# RX08-8-9.net
KiCad netlist of a schematic drawn in EAGLE
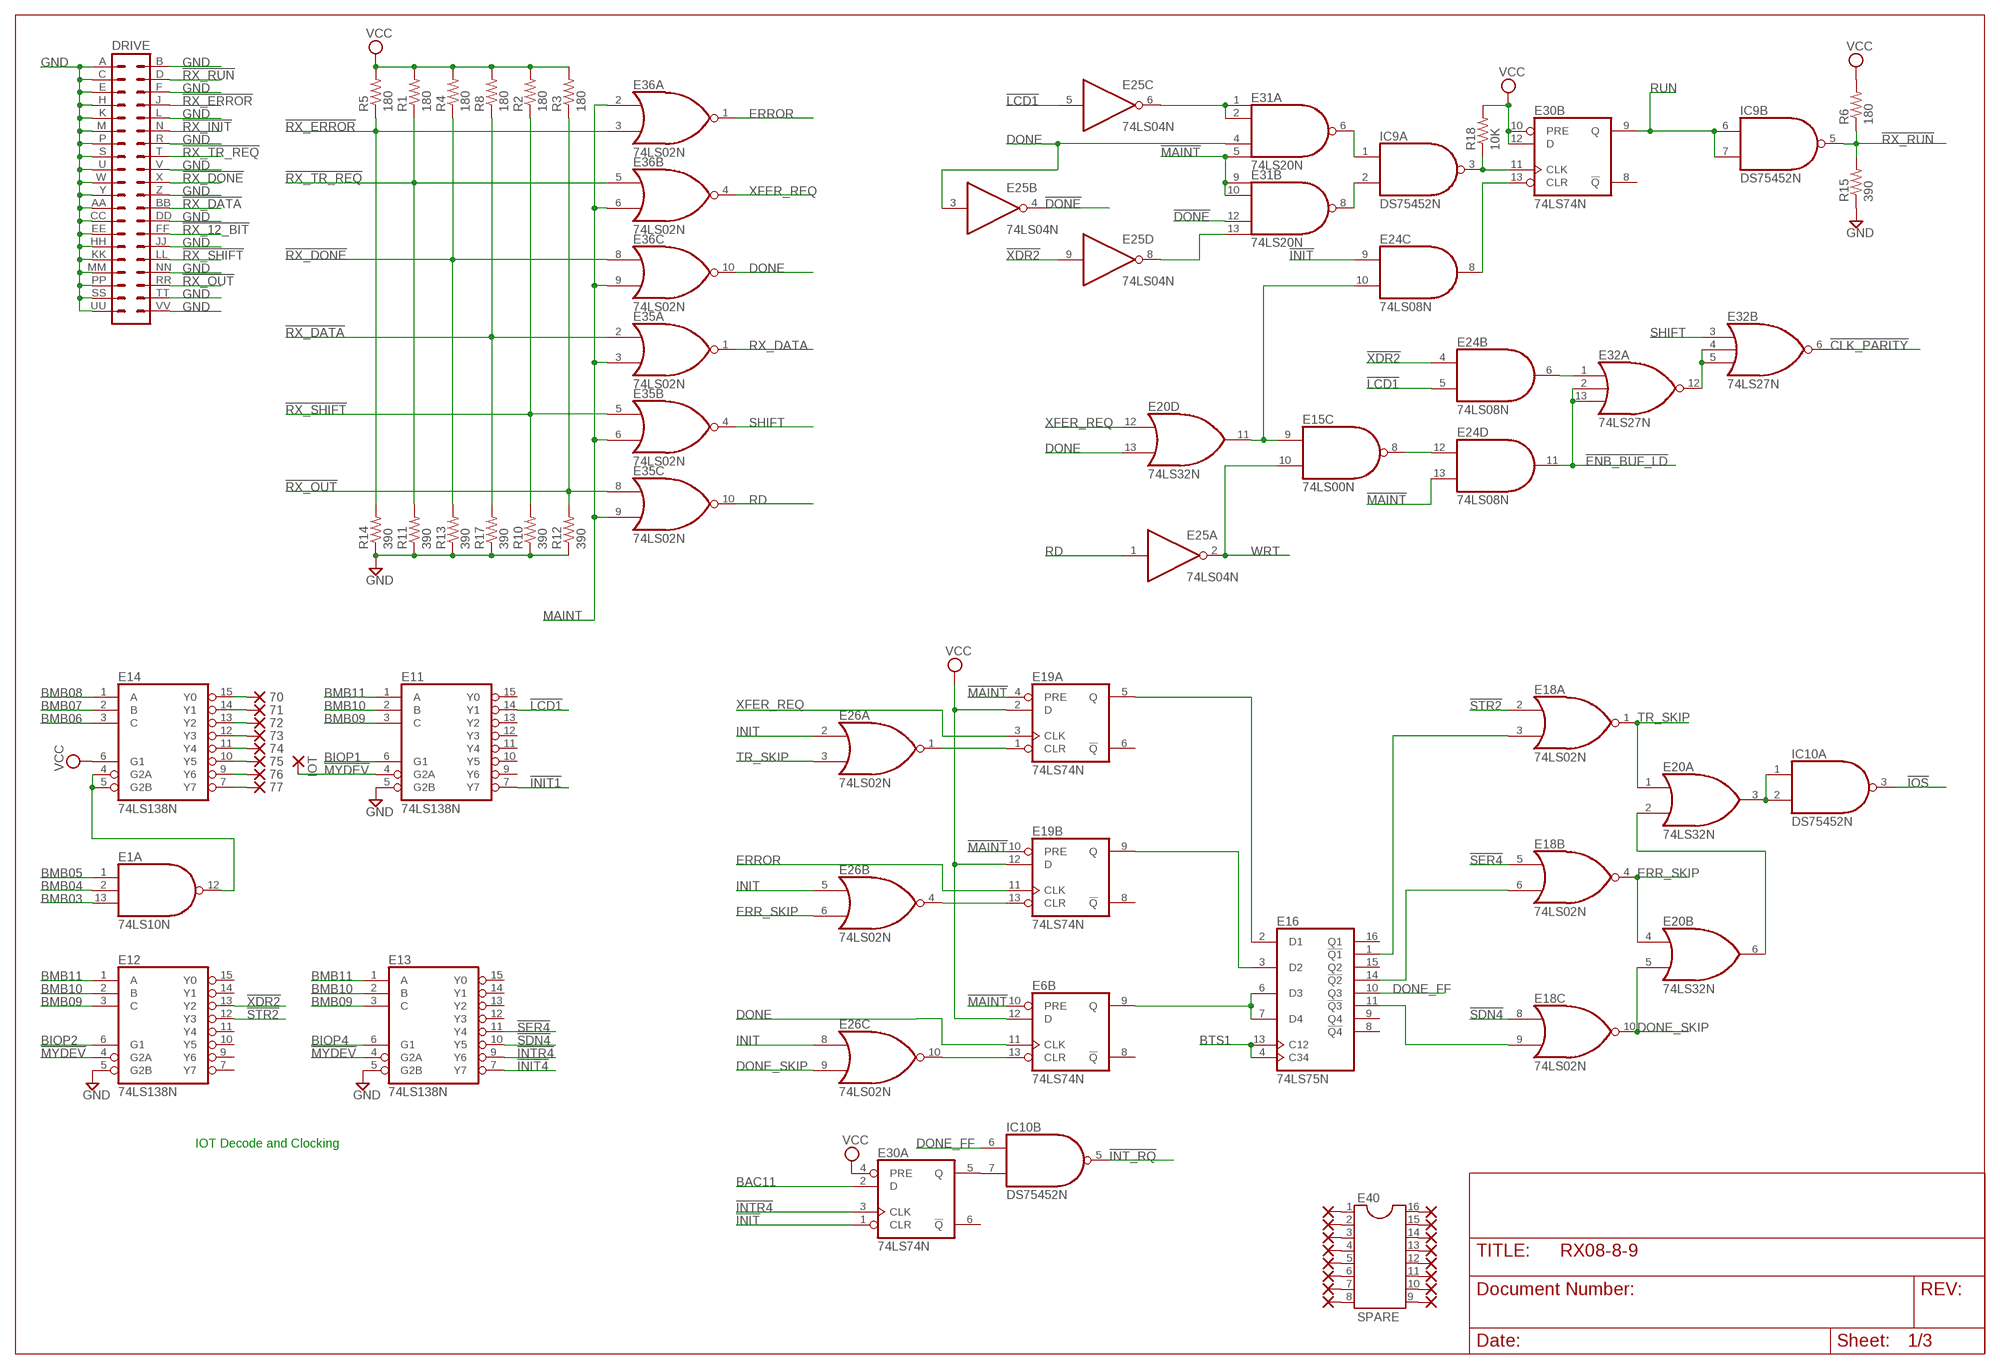
[diagram p0: schematic, sheet 1]
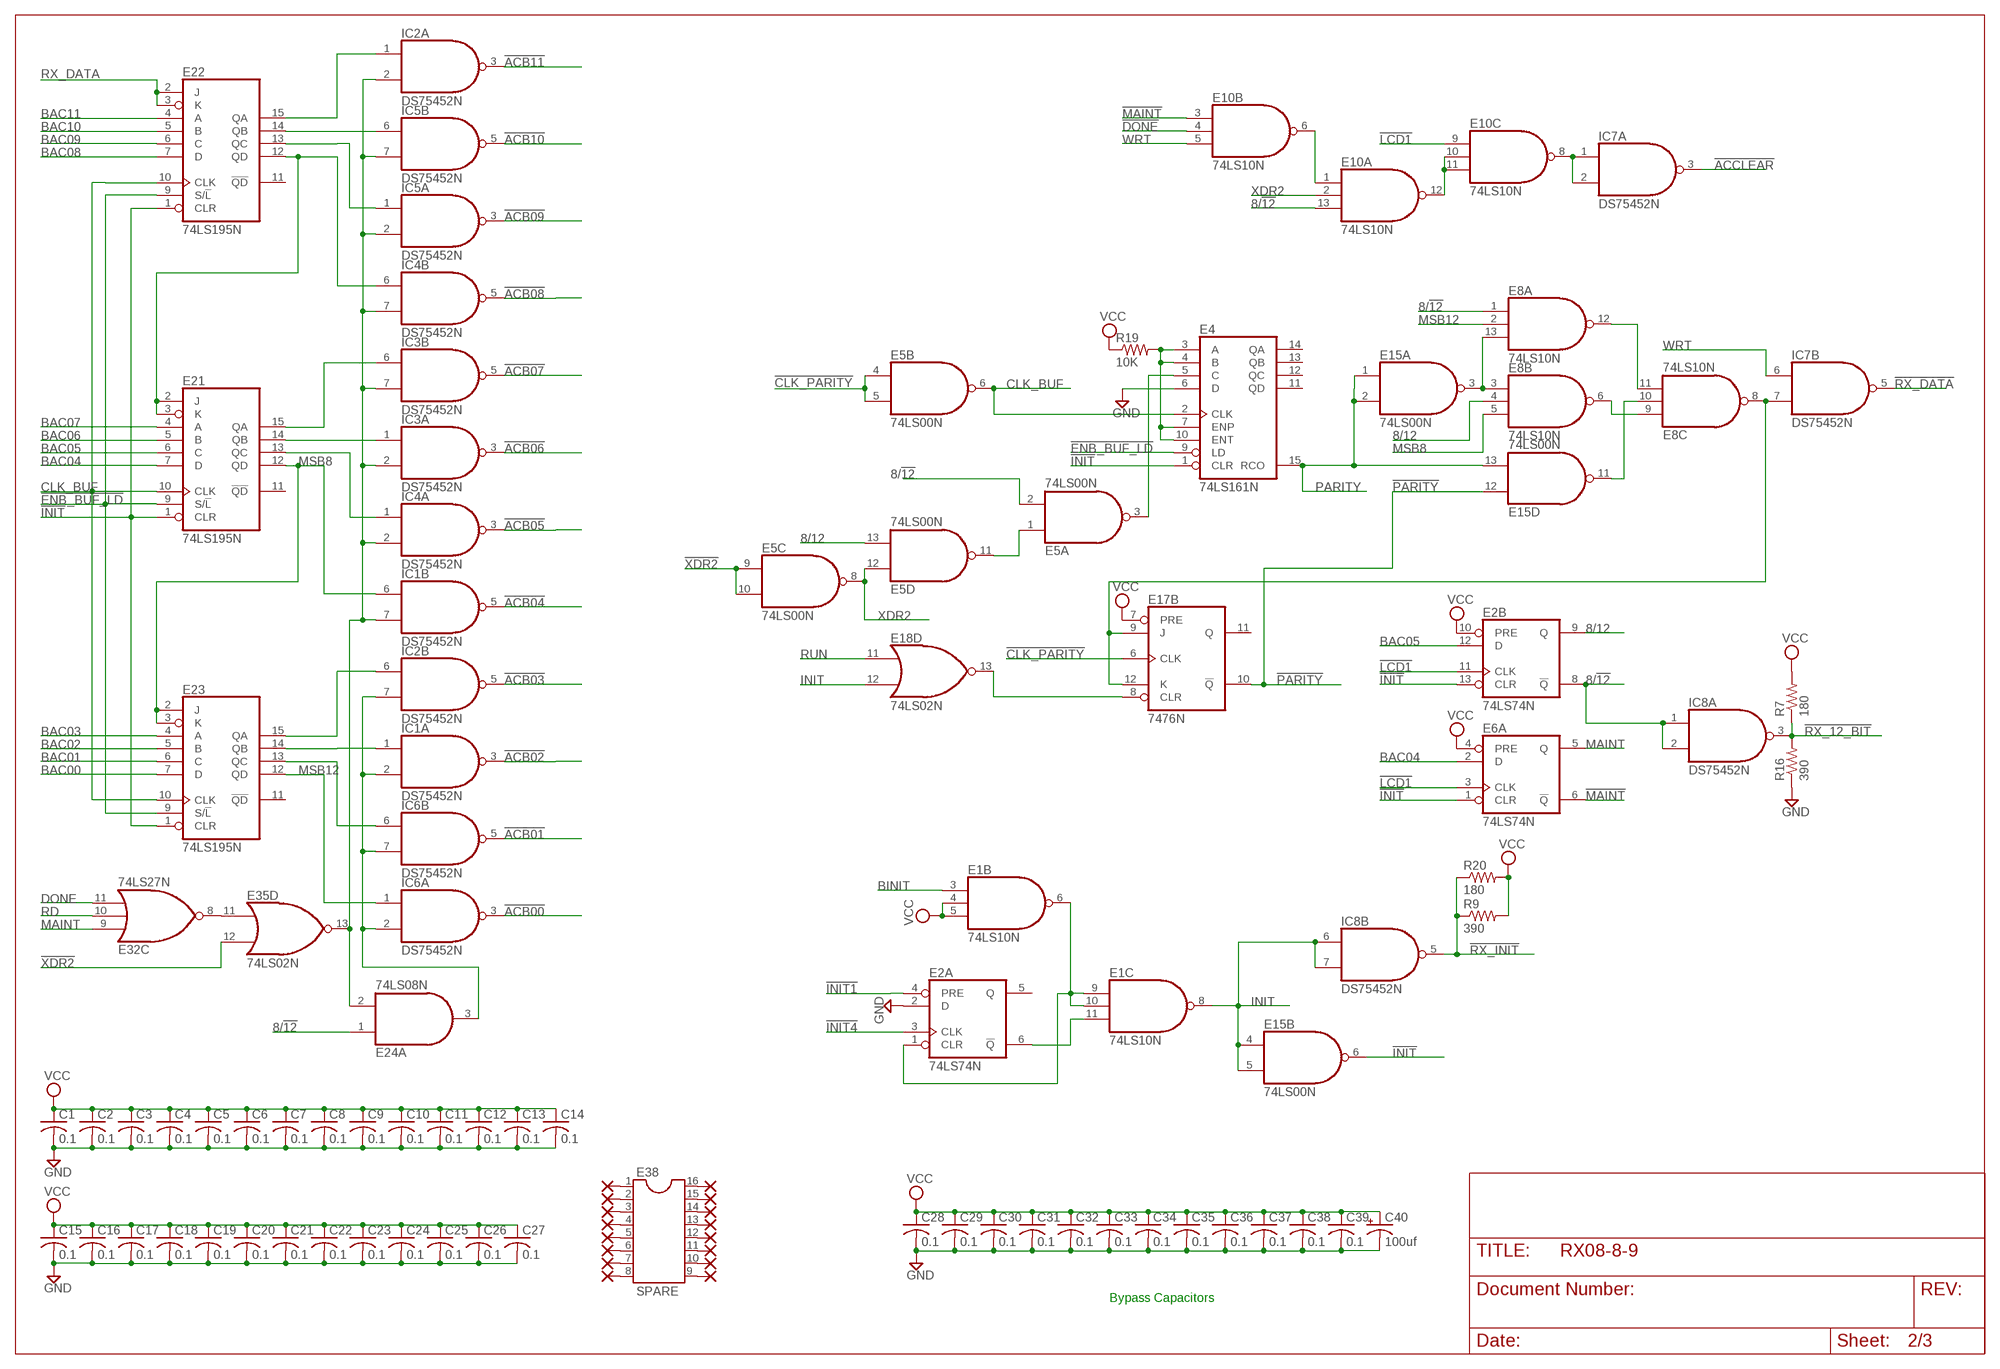
[diagram p1: schematic, sheet 2]
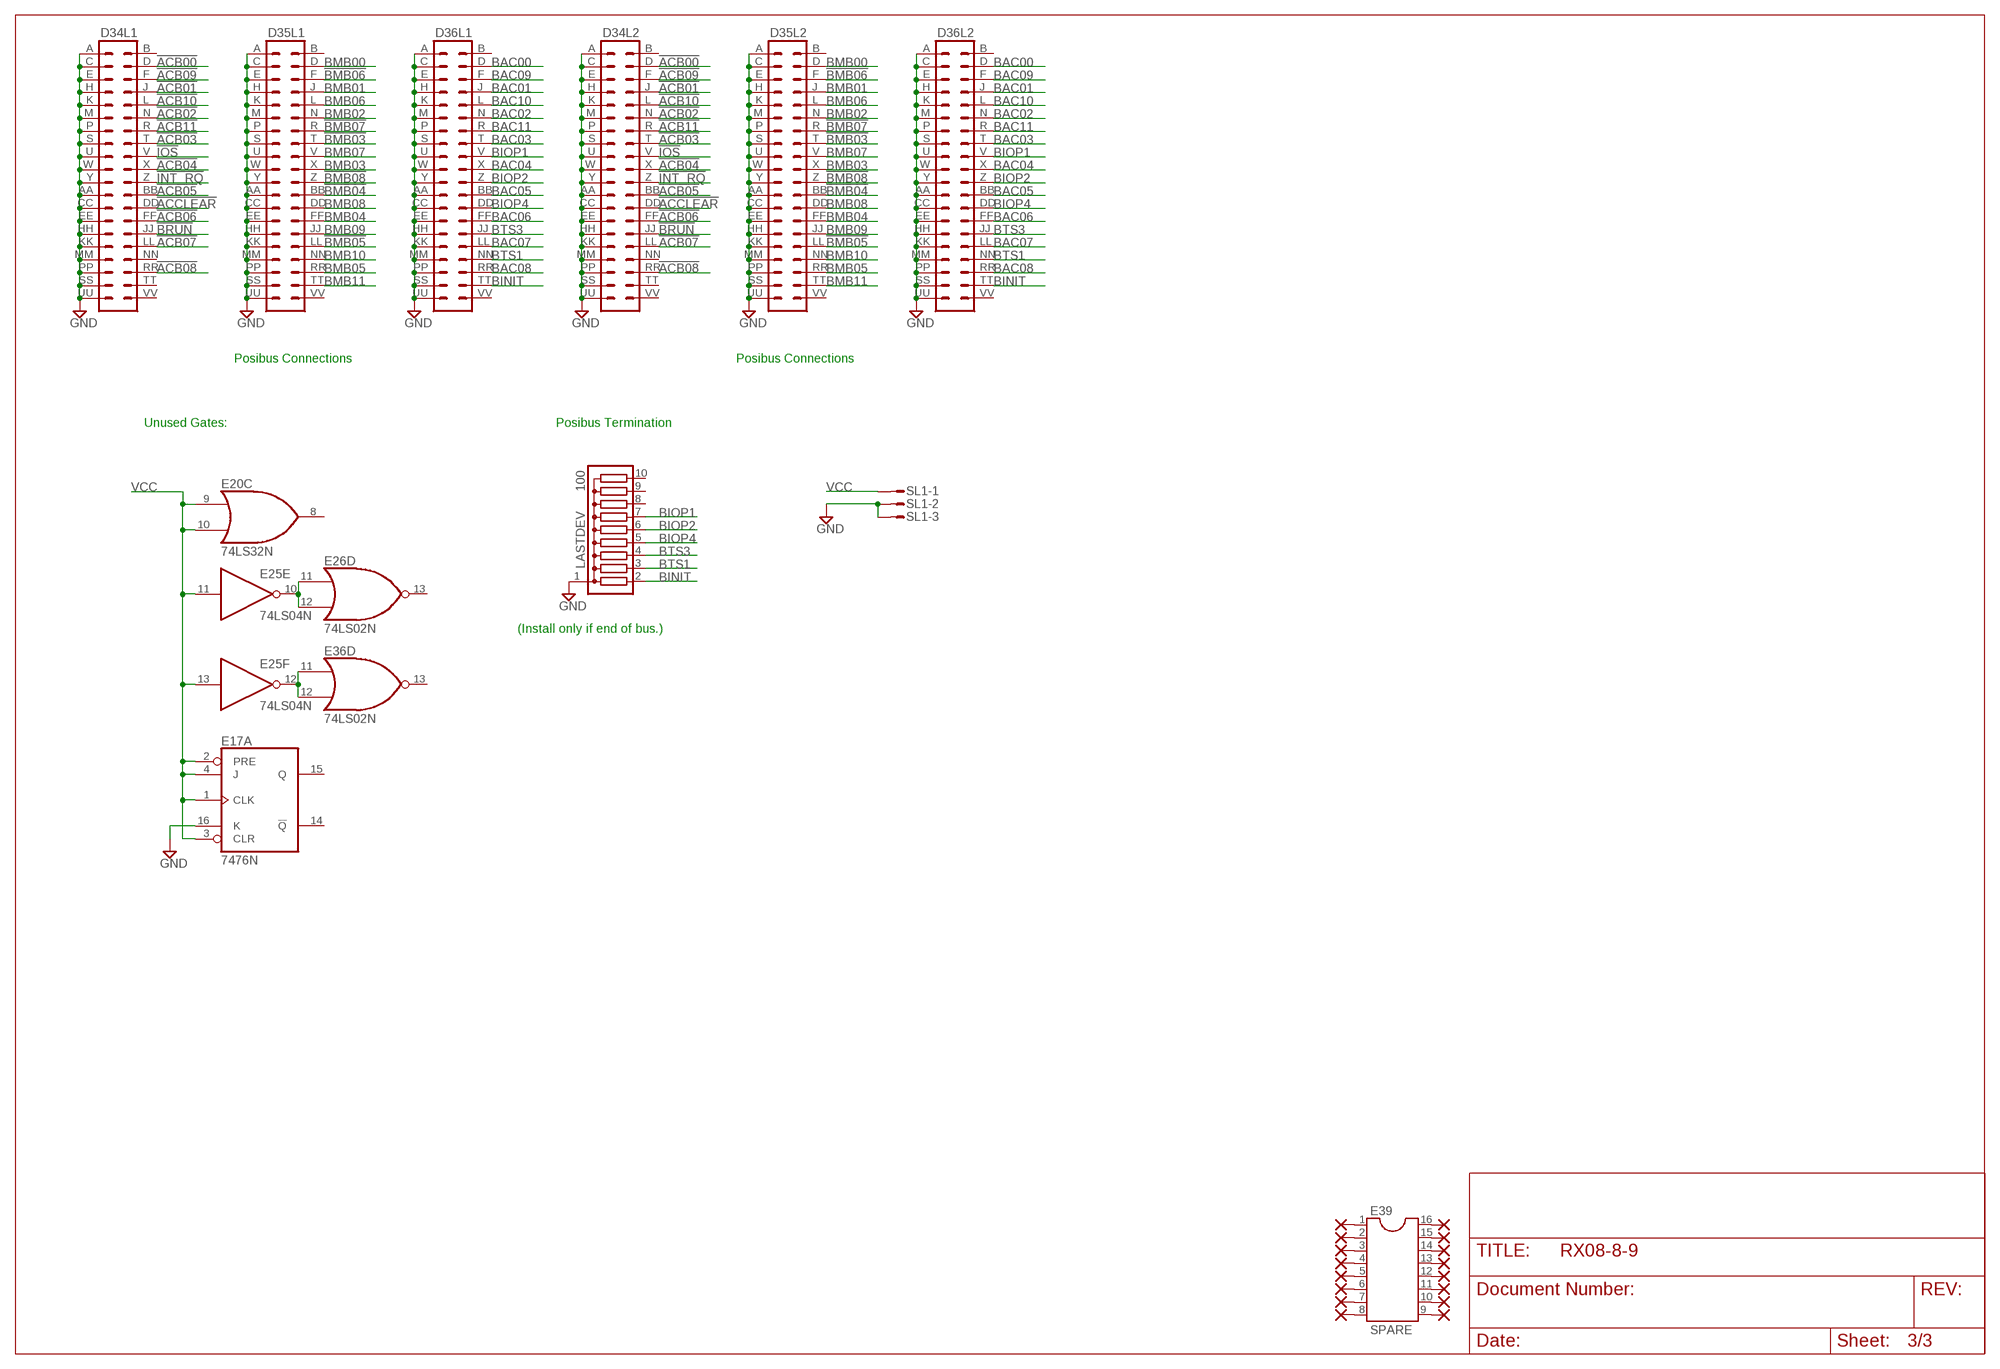
[diagram p2: schematic, sheet 3]

(export (version "E")
  (design (tool "Eeschema 10.0.6"))
  (components
    (comp (ref "D34L1")
      (value "DEC40PINV")
      (footprint "eagle-import:DEC40PINV")
      (libsource (lib "eagle-import") (part "DEC40PINV"))
    )
    (comp (ref "D34L2")
      (value "DEC40PINV")
      (footprint "eagle-import:DEC40PINV")
      (libsource (lib "eagle-import") (part "DEC40PINV"))
    )
    (comp (ref "D35L1")
      (value "DEC40PINV")
      (footprint "eagle-import:DEC40PINV")
      (libsource (lib "eagle-import") (part "DEC40PINV"))
    )
    (comp (ref "D35L2")
      (value "DEC40PINV")
      (footprint "eagle-import:DEC40PINV")
      (libsource (lib "eagle-import") (part "DEC40PINV"))
    )
    (comp (ref "D36L1")
      (value "DEC40PINV")
      (footprint "eagle-import:DEC40PINV")
      (libsource (lib "eagle-import") (part "DEC40PINV"))
    )
    (comp (ref "D36L2")
      (value "DEC40PINV")
      (footprint "eagle-import:DEC40PINV")
      (libsource (lib "eagle-import") (part "DEC40PINV"))
    )
    (comp (ref "E17")
      (value "7476N")
      (footprint "eagle-import:DIL16")
      (libsource (lib "eagle-import") (part "7476N"))
    )
    (comp (ref "E20")
      (value "74LS32N")
      (footprint "eagle-import:DIL14")
      (libsource (lib "eagle-import") (part "7432NLS"))
    )
    (comp (ref "E25")
      (value "74LS04N")
      (footprint "eagle-import:DIL14")
      (libsource (lib "eagle-import") (part "7404NLS"))
    )
    (comp (ref "E26")
      (value "74LS02N")
      (footprint "eagle-import:DIL14")
      (libsource (lib "eagle-import") (part "7402NLS"))
    )
    (comp (ref "E36")
      (value "74LS02N")
      (footprint "eagle-import:DIL14")
      (libsource (lib "eagle-import") (part "7402NLS"))
    )
    (comp (ref "E39")
      (value "SPARE")
      (footprint "eagle-import:DIL16")
      (libsource (lib "eagle-import") (part "DIL16"))
    )
    (comp (ref "LASTDEV")
      (value "100")
      (footprint "eagle-import:SIL10")
      (libsource (lib "eagle-import") (part "G09R"))
    )
    (comp (ref "PAD42")
      (value "1,6/0,8")
      (footprint "eagle-import:1,6_0,8")
      (libsource (lib "eagle-import") (part "1,6/0,8"))
    )
    (comp (ref "PAD43")
      (value "1,6/0,8")
      (footprint "eagle-import:1,6_0,8")
      (libsource (lib "eagle-import") (part "1,6/0,8"))
    )
    (comp (ref "PAD44")
      (value "1,6/0,8")
      (footprint "eagle-import:1,6_0,8")
      (libsource (lib "eagle-import") (part "1,6/0,8"))
    )
    (comp (ref "PAD45")
      (value "1,6/0,8")
      (footprint "eagle-import:1,6_0,8")
      (libsource (lib "eagle-import") (part "1,6/0,8"))
    )
    (comp (ref "PAD46")
      (value "1,6/0,8")
      (footprint "eagle-import:1,6_0,8")
      (libsource (lib "eagle-import") (part "1,6/0,8"))
    )
    (comp (ref "PAD47")
      (value "1,6/0,8")
      (footprint "eagle-import:1,6_0,8")
      (libsource (lib "eagle-import") (part "1,6/0,8"))
    )
    (comp (ref "PAD48")
      (value "1,6/0,8")
      (footprint "eagle-import:1,6_0,8")
      (libsource (lib "eagle-import") (part "1,6/0,8"))
    )
    (comp (ref "PAD49")
      (value "1,6/0,8")
      (footprint "eagle-import:1,6_0,8")
      (libsource (lib "eagle-import") (part "1,6/0,8"))
    )
    (comp (ref "PAD50")
      (value "1,6/0,8")
      (footprint "eagle-import:1,6_0,8")
      (libsource (lib "eagle-import") (part "1,6/0,8"))
    )
    (comp (ref "PAD51")
      (value "1,6/0,8")
      (footprint "eagle-import:1,6_0,8")
      (libsource (lib "eagle-import") (part "1,6/0,8"))
    )
    (comp (ref "PAD52")
      (value "1,6/0,8")
      (footprint "eagle-import:1,6_0,8")
      (libsource (lib "eagle-import") (part "1,6/0,8"))
    )
    (comp (ref "PAD53")
      (value "1,6/0,8")
      (footprint "eagle-import:1,6_0,8")
      (libsource (lib "eagle-import") (part "1,6/0,8"))
    )
    (comp (ref "PAD54")
      (value "1,6/0,8")
      (footprint "eagle-import:1,6_0,8")
      (libsource (lib "eagle-import") (part "1,6/0,8"))
    )
    (comp (ref "PAD55")
      (value "1,6/0,8")
      (footprint "eagle-import:1,6_0,8")
      (libsource (lib "eagle-import") (part "1,6/0,8"))
    )
    (comp (ref "PAD56")
      (value "1,6/0,8")
      (footprint "eagle-import:1,6_0,8")
      (libsource (lib "eagle-import") (part "1,6/0,8"))
    )
    (comp (ref "PAD57")
      (value "1,6/0,8")
      (footprint "eagle-import:1,6_0,8")
      (libsource (lib "eagle-import") (part "1,6/0,8"))
    )
    (comp (ref "SL1")
      (value "MA04S")
      (footprint "eagle-import:04PA")
      (libsource (lib "eagle-import") (part "MA04S"))
    )
    (comp (ref "C1")
      (value "0.1")
      (footprint "eagle-import:C050-025X075")
      (libsource (lib "eagle-import") (part "C-US050-025X075"))
    )
    (comp (ref "C2")
      (value "0.1")
      (footprint "eagle-import:C050-025X075")
      (libsource (lib "eagle-import") (part "C-US050-025X075"))
    )
    (comp (ref "C3")
      (value "0.1")
      (footprint "eagle-import:C050-025X075")
      (libsource (lib "eagle-import") (part "C-US050-025X075"))
    )
    (comp (ref "C4")
      (value "0.1")
      (footprint "eagle-import:C050-025X075")
      (libsource (lib "eagle-import") (part "C-US050-025X075"))
    )
    (comp (ref "C5")
      (value "0.1")
      (footprint "eagle-import:C050-025X075")
      (libsource (lib "eagle-import") (part "C-US050-025X075"))
    )
    (comp (ref "C6")
      (value "0.1")
      (footprint "eagle-import:C050-025X075")
      (libsource (lib "eagle-import") (part "C-US050-025X075"))
    )
    (comp (ref "C7")
      (value "0.1")
      (footprint "eagle-import:C050-025X075")
      (libsource (lib "eagle-import") (part "C-US050-025X075"))
    )
    (comp (ref "C8")
      (value "0.1")
      (footprint "eagle-import:C050-025X075")
      (libsource (lib "eagle-import") (part "C-US050-025X075"))
    )
    (comp (ref "C9")
      (value "0.1")
      (footprint "eagle-import:C050-025X075")
      (libsource (lib "eagle-import") (part "C-US050-025X075"))
    )
    (comp (ref "C10")
      (value "0.1")
      (footprint "eagle-import:C050-025X075")
      (libsource (lib "eagle-import") (part "C-US050-025X075"))
    )
    (comp (ref "C11")
      (value "0.1")
      (footprint "eagle-import:C050-025X075")
      (libsource (lib "eagle-import") (part "C-US050-025X075"))
    )
    (comp (ref "C12")
      (value "0.1")
      (footprint "eagle-import:C050-025X075")
      (libsource (lib "eagle-import") (part "C-US050-025X075"))
    )
    (comp (ref "C13")
      (value "0.1")
      (footprint "eagle-import:C050-025X075")
      (libsource (lib "eagle-import") (part "C-US050-025X075"))
    )
    (comp (ref "C14")
      (value "0.1")
      (footprint "eagle-import:C050-025X075")
      (libsource (lib "eagle-import") (part "C-US050-025X075"))
    )
    (comp (ref "C15")
      (value "0.1")
      (footprint "eagle-import:C050-025X075")
      (libsource (lib "eagle-import") (part "C-US050-025X075"))
    )
    (comp (ref "C16")
      (value "0.1")
      (footprint "eagle-import:C050-025X075")
      (libsource (lib "eagle-import") (part "C-US050-025X075"))
    )
    (comp (ref "C17")
      (value "0.1")
      (footprint "eagle-import:C050-025X075")
      (libsource (lib "eagle-import") (part "C-US050-025X075"))
    )
    (comp (ref "C18")
      (value "0.1")
      (footprint "eagle-import:C050-025X075")
      (libsource (lib "eagle-import") (part "C-US050-025X075"))
    )
    (comp (ref "C19")
      (value "0.1")
      (footprint "eagle-import:C050-025X075")
      (libsource (lib "eagle-import") (part "C-US050-025X075"))
    )
    (comp (ref "C20")
      (value "0.1")
      (footprint "eagle-import:C050-025X075")
      (libsource (lib "eagle-import") (part "C-US050-025X075"))
    )
    (comp (ref "C21")
      (value "0.1")
      (footprint "eagle-import:C050-025X075")
      (libsource (lib "eagle-import") (part "C-US050-025X075"))
    )
    (comp (ref "C22")
      (value "0.1")
      (footprint "eagle-import:C050-025X075")
      (libsource (lib "eagle-import") (part "C-US050-025X075"))
    )
    (comp (ref "C23")
      (value "0.1")
      (footprint "eagle-import:C050-025X075")
      (libsource (lib "eagle-import") (part "C-US050-025X075"))
    )
    (comp (ref "C24")
      (value "0.1")
      (footprint "eagle-import:C050-025X075")
      (libsource (lib "eagle-import") (part "C-US050-025X075"))
    )
    (comp (ref "C25")
      (value "0.1")
      (footprint "eagle-import:C050-025X075")
      (libsource (lib "eagle-import") (part "C-US050-025X075"))
    )
    (comp (ref "C26")
      (value "0.1")
      (footprint "eagle-import:C050-025X075")
      (libsource (lib "eagle-import") (part "C-US050-025X075"))
    )
    (comp (ref "C27")
      (value "0.1")
      (footprint "eagle-import:C050-025X075")
      (libsource (lib "eagle-import") (part "C-US050-025X075"))
    )
    (comp (ref "C28")
      (value "0.1")
      (footprint "eagle-import:C050-025X075")
      (libsource (lib "eagle-import") (part "C-US050-025X075"))
    )
    (comp (ref "C29")
      (value "0.1")
      (footprint "eagle-import:C050-025X075")
      (libsource (lib "eagle-import") (part "C-US050-025X075"))
    )
    (comp (ref "C30")
      (value "0.1")
      (footprint "eagle-import:C050-025X075")
      (libsource (lib "eagle-import") (part "C-US050-025X075"))
    )
    (comp (ref "C31")
      (value "0.1")
      (footprint "eagle-import:C050-025X075")
      (libsource (lib "eagle-import") (part "C-US050-025X075"))
    )
    (comp (ref "C32")
      (value "0.1")
      (footprint "eagle-import:C050-025X075")
      (libsource (lib "eagle-import") (part "C-US050-025X075"))
    )
    (comp (ref "C33")
      (value "0.1")
      (footprint "eagle-import:C050-025X075")
      (libsource (lib "eagle-import") (part "C-US050-025X075"))
    )
    (comp (ref "C34")
      (value "0.1")
      (footprint "eagle-import:C050-025X075")
      (libsource (lib "eagle-import") (part "C-US050-025X075"))
    )
    (comp (ref "C35")
      (value "0.1")
      (footprint "eagle-import:C050-025X075")
      (libsource (lib "eagle-import") (part "C-US050-025X075"))
    )
    (comp (ref "C36")
      (value "0.1")
      (footprint "eagle-import:C050-025X075")
      (libsource (lib "eagle-import") (part "C-US050-025X075"))
    )
    (comp (ref "C37")
      (value "0.1")
      (footprint "eagle-import:C050-025X075")
      (libsource (lib "eagle-import") (part "C-US050-025X075"))
    )
    (comp (ref "C38")
      (value "0.1")
      (footprint "eagle-import:C050-025X075")
      (libsource (lib "eagle-import") (part "C-US050-025X075"))
    )
    (comp (ref "C39")
      (value "0.1")
      (footprint "eagle-import:C050-025X075")
      (libsource (lib "eagle-import") (part "C-US050-025X075"))
    )
    (comp (ref "C40")
      (value "100uf")
      (footprint "eagle-import:E22-9")
      (libsource (lib "eagle-import") (part "CPOL-USE22-9AXIAL"))
    )
    (comp (ref "E1")
      (value "74LS10N")
      (footprint "eagle-import:DIL14")
      (libsource (lib "eagle-import") (part "7410NLS"))
    )
    (comp (ref "E2")
      (value "74LS74N")
      (footprint "eagle-import:DIL14")
      (libsource (lib "eagle-import") (part "7474NLS"))
    )
    (comp (ref "E4")
      (value "74LS161N")
      (footprint "eagle-import:DIL16")
      (libsource (lib "eagle-import") (part "74161NLS"))
    )
    (comp (ref "E5")
      (value "74LS00N")
      (footprint "eagle-import:DIL14")
      (libsource (lib "eagle-import") (part "7400NLS"))
    )
    (comp (ref "E6")
      (value "74LS74N")
      (footprint "eagle-import:DIL14")
      (libsource (lib "eagle-import") (part "7474NLS"))
    )
    (comp (ref "E8")
      (value "74LS10N")
      (footprint "eagle-import:DIL14")
      (libsource (lib "eagle-import") (part "7410NLS"))
    )
    (comp (ref "E10")
      (value "74LS10N")
      (footprint "eagle-import:DIL14")
      (libsource (lib "eagle-import") (part "7410NLS"))
    )
    (comp (ref "E15")
      (value "74LS00N")
      (footprint "eagle-import:DIL14")
      (libsource (lib "eagle-import") (part "7400NLS"))
    )
    (comp (ref "E18")
      (value "74LS02N")
      (footprint "eagle-import:DIL14")
      (libsource (lib "eagle-import") (part "7402NLS"))
    )
    (comp (ref "E21")
      (value "74LS195N")
      (footprint "eagle-import:DIL16")
      (libsource (lib "eagle-import") (part "74195NLS"))
    )
    (comp (ref "E22")
      (value "74LS195N")
      (footprint "eagle-import:DIL16")
      (libsource (lib "eagle-import") (part "74195NLS"))
    )
    (comp (ref "E23")
      (value "74LS195N")
      (footprint "eagle-import:DIL16")
      (libsource (lib "eagle-import") (part "74195NLS"))
    )
    (comp (ref "E24")
      (value "74LS08N")
      (footprint "eagle-import:DIL14")
      (libsource (lib "eagle-import") (part "7408NLS"))
    )
    (comp (ref "E32")
      (value "74LS27N")
      (footprint "eagle-import:DIL14")
      (libsource (lib "eagle-import") (part "7427NLS"))
    )
    (comp (ref "E35")
      (value "74LS02N")
      (footprint "eagle-import:DIL14")
      (libsource (lib "eagle-import") (part "7402NLS"))
    )
    (comp (ref "E38")
      (value "SPARE")
      (footprint "eagle-import:DIL16")
      (libsource (lib "eagle-import") (part "DIL16"))
    )
    (comp (ref "IC1")
      (value "DS75452N")
      (footprint "eagle-import:DIL08")
      (libsource (lib "eagle-import") (part "DS75452N"))
    )
    (comp (ref "IC2")
      (value "DS75452N")
      (footprint "eagle-import:DIL08")
      (libsource (lib "eagle-import") (part "DS75452N"))
    )
    (comp (ref "IC3")
      (value "DS75452N")
      (footprint "eagle-import:DIL08")
      (libsource (lib "eagle-import") (part "DS75452N"))
    )
    (comp (ref "IC4")
      (value "DS75452N")
      (footprint "eagle-import:DIL08")
      (libsource (lib "eagle-import") (part "DS75452N"))
    )
    (comp (ref "IC5")
      (value "DS75452N")
      (footprint "eagle-import:DIL08")
      (libsource (lib "eagle-import") (part "DS75452N"))
    )
    (comp (ref "IC6")
      (value "DS75452N")
      (footprint "eagle-import:DIL08")
      (libsource (lib "eagle-import") (part "DS75452N"))
    )
    (comp (ref "IC7")
      (value "DS75452N")
      (footprint "eagle-import:DIL08")
      (libsource (lib "eagle-import") (part "DS75452N"))
    )
    (comp (ref "IC8")
      (value "DS75452N")
      (footprint "eagle-import:DIL08")
      (libsource (lib "eagle-import") (part "DS75452N"))
    )
    (comp (ref "PAD10")
      (value "1,6/0,8")
      (footprint "eagle-import:1,6_0,8")
      (libsource (lib "eagle-import") (part "1,6/0,8"))
    )
    (comp (ref "PAD11")
      (value "1,6/0,8")
      (footprint "eagle-import:1,6_0,8")
      (libsource (lib "eagle-import") (part "1,6/0,8"))
    )
    (comp (ref "PAD12")
      (value "1,6/0,8")
      (footprint "eagle-import:1,6_0,8")
      (libsource (lib "eagle-import") (part "1,6/0,8"))
    )
    (comp (ref "PAD13")
      (value "1,6/0,8")
      (footprint "eagle-import:1,6_0,8")
      (libsource (lib "eagle-import") (part "1,6/0,8"))
    )
    (comp (ref "PAD14")
      (value "1,6/0,8")
      (footprint "eagle-import:1,6_0,8")
      (libsource (lib "eagle-import") (part "1,6/0,8"))
    )
    (comp (ref "PAD15")
      (value "1,6/0,8")
      (footprint "eagle-import:1,6_0,8")
      (libsource (lib "eagle-import") (part "1,6/0,8"))
    )
    (comp (ref "PAD16")
      (value "1,6/0,8")
      (footprint "eagle-import:1,6_0,8")
      (libsource (lib "eagle-import") (part "1,6/0,8"))
    )
    (comp (ref "PAD17")
      (value "1,6/0,8")
      (footprint "eagle-import:1,6_0,8")
      (libsource (lib "eagle-import") (part "1,6/0,8"))
    )
    (comp (ref "PAD20")
      (value "1,6/0,8")
      (footprint "eagle-import:1,6_0,8")
      (libsource (lib "eagle-import") (part "1,6/0,8"))
    )
    (comp (ref "PAD21")
      (value "1,6/0,8")
      (footprint "eagle-import:1,6_0,8")
      (libsource (lib "eagle-import") (part "1,6/0,8"))
    )
    (comp (ref "PAD22")
      (value "1,6/0,8")
      (footprint "eagle-import:1,6_0,8")
      (libsource (lib "eagle-import") (part "1,6/0,8"))
    )
    (comp (ref "PAD23")
      (value "1,6/0,8")
      (footprint "eagle-import:1,6_0,8")
      (libsource (lib "eagle-import") (part "1,6/0,8"))
    )
    (comp (ref "PAD24")
      (value "1,6/0,8")
      (footprint "eagle-import:1,6_0,8")
      (libsource (lib "eagle-import") (part "1,6/0,8"))
    )
    (comp (ref "PAD25")
      (value "1,6/0,8")
      (footprint "eagle-import:1,6_0,8")
      (libsource (lib "eagle-import") (part "1,6/0,8"))
    )
    (comp (ref "PAD26")
      (value "1,6/0,8")
      (footprint "eagle-import:1,6_0,8")
      (libsource (lib "eagle-import") (part "1,6/0,8"))
    )
    (comp (ref "PAD27")
      (value "1,6/0,8")
      (footprint "eagle-import:1,6_0,8")
      (libsource (lib "eagle-import") (part "1,6/0,8"))
    )
    (comp (ref "R7")
      (value "180")
      (footprint "eagle-import:0207_10")
      (libsource (lib "eagle-import") (part "R-US_0207/10"))
    )
    (comp (ref "R9")
      (value "390")
      (footprint "eagle-import:0207_10")
      (libsource (lib "eagle-import") (part "R-US_0207/10"))
    )
    (comp (ref "R16")
      (value "390")
      (footprint "eagle-import:0207_10")
      (libsource (lib "eagle-import") (part "R-US_0207/10"))
    )
    (comp (ref "R19")
      (value "10K")
      (footprint "eagle-import:0207_10")
      (libsource (lib "eagle-import") (part "R-US_0207/10"))
    )
    (comp (ref "R20")
      (value "180")
      (footprint "eagle-import:0207_10")
      (libsource (lib "eagle-import") (part "R-US_0207/10"))
    )
    (comp (ref "70")
      (value "1,6/0,8")
      (footprint "eagle-import:1,6_0,8")
      (libsource (lib "eagle-import") (part "1,6/0,8"))
    )
    (comp (ref "71")
      (value "1,6/0,8")
      (footprint "eagle-import:1,6_0,8")
      (libsource (lib "eagle-import") (part "1,6/0,8"))
    )
    (comp (ref "72")
      (value "1,6/0,8")
      (footprint "eagle-import:1,6_0,8")
      (libsource (lib "eagle-import") (part "1,6/0,8"))
    )
    (comp (ref "73")
      (value "1,6/0,8")
      (footprint "eagle-import:1,6_0,8")
      (libsource (lib "eagle-import") (part "1,6/0,8"))
    )
    (comp (ref "74")
      (value "1,6/0,8")
      (footprint "eagle-import:1,6_0,8")
      (libsource (lib "eagle-import") (part "1,6/0,8"))
    )
    (comp (ref "75")
      (value "1,6/0,8")
      (footprint "eagle-import:1,6_0,8")
      (libsource (lib "eagle-import") (part "1,6/0,8"))
    )
    (comp (ref "76")
      (value "1,6/0,8")
      (footprint "eagle-import:1,6_0,8")
      (libsource (lib "eagle-import") (part "1,6/0,8"))
    )
    (comp (ref "77")
      (value "1,6/0,8")
      (footprint "eagle-import:1,6_0,8")
      (libsource (lib "eagle-import") (part "1,6/0,8"))
    )
    (comp (ref "DRIVE")
      (value "DEC40PINV")
      (footprint "eagle-import:DEC40PINV")
      (libsource (lib "eagle-import") (part "DEC40PINV"))
    )
    (comp (ref "E11")
      (value "74LS138N")
      (footprint "eagle-import:DIL16")
      (libsource (lib "eagle-import") (part "74138NLS"))
    )
    (comp (ref "E12")
      (value "74LS138N")
      (footprint "eagle-import:DIL16")
      (libsource (lib "eagle-import") (part "74138NLS"))
    )
    (comp (ref "E13")
      (value "74LS138N")
      (footprint "eagle-import:DIL16")
      (libsource (lib "eagle-import") (part "74138NLS"))
    )
    (comp (ref "E14")
      (value "74LS138N")
      (footprint "eagle-import:DIL16")
      (libsource (lib "eagle-import") (part "74138NLS"))
    )
    (comp (ref "E16")
      (value "74LS75N")
      (footprint "eagle-import:DIL16")
      (libsource (lib "eagle-import") (part "7475NLS"))
    )
    (comp (ref "E19")
      (value "74LS74N")
      (footprint "eagle-import:DIL14")
      (libsource (lib "eagle-import") (part "7474NLS"))
    )
    (comp (ref "E30")
      (value "74LS74N")
      (footprint "eagle-import:DIL14")
      (libsource (lib "eagle-import") (part "7474NLS"))
    )
    (comp (ref "E31")
      (value "74LS20N")
      (footprint "eagle-import:DIL14")
      (libsource (lib "eagle-import") (part "7420NLS"))
    )
    (comp (ref "E40")
      (value "SPARE")
      (footprint "eagle-import:DIL16")
      (libsource (lib "eagle-import") (part "DIL16"))
    )
    (comp (ref "IC9")
      (value "DS75452N")
      (footprint "eagle-import:DIL08")
      (libsource (lib "eagle-import") (part "DS75452N"))
    )
    (comp (ref "IC10")
      (value "DS75452N")
      (footprint "eagle-import:DIL08")
      (libsource (lib "eagle-import") (part "DS75452N"))
    )
    (comp (ref "IOT")
      (value "1,6/0,8")
      (footprint "eagle-import:1,6_0,8")
      (libsource (lib "eagle-import") (part "1,6/0,8"))
    )
    (comp (ref "PAD18")
      (value "1,6/0,8")
      (footprint "eagle-import:1,6_0,8")
      (libsource (lib "eagle-import") (part "1,6/0,8"))
    )
    (comp (ref "PAD19")
      (value "1,6/0,8")
      (footprint "eagle-import:1,6_0,8")
      (libsource (lib "eagle-import") (part "1,6/0,8"))
    )
    (comp (ref "PAD28")
      (value "1,6/0,8")
      (footprint "eagle-import:1,6_0,8")
      (libsource (lib "eagle-import") (part "1,6/0,8"))
    )
    (comp (ref "PAD29")
      (value "1,6/0,8")
      (footprint "eagle-import:1,6_0,8")
      (libsource (lib "eagle-import") (part "1,6/0,8"))
    )
    (comp (ref "PAD30")
      (value "1,6/0,8")
      (footprint "eagle-import:1,6_0,8")
      (libsource (lib "eagle-import") (part "1,6/0,8"))
    )
    (comp (ref "PAD31")
      (value "1,6/0,8")
      (footprint "eagle-import:1,6_0,8")
      (libsource (lib "eagle-import") (part "1,6/0,8"))
    )
    (comp (ref "PAD32")
      (value "1,6/0,8")
      (footprint "eagle-import:1,6_0,8")
      (libsource (lib "eagle-import") (part "1,6/0,8"))
    )
    (comp (ref "PAD33")
      (value "1,6/0,8")
      (footprint "eagle-import:1,6_0,8")
      (libsource (lib "eagle-import") (part "1,6/0,8"))
    )
    (comp (ref "PAD34")
      (value "1,6/0,8")
      (footprint "eagle-import:1,6_0,8")
      (libsource (lib "eagle-import") (part "1,6/0,8"))
    )
    (comp (ref "PAD35")
      (value "1,6/0,8")
      (footprint "eagle-import:1,6_0,8")
      (libsource (lib "eagle-import") (part "1,6/0,8"))
    )
    (comp (ref "PAD36")
      (value "1,6/0,8")
      (footprint "eagle-import:1,6_0,8")
      (libsource (lib "eagle-import") (part "1,6/0,8"))
    )
    (comp (ref "PAD37")
      (value "1,6/0,8")
      (footprint "eagle-import:1,6_0,8")
      (libsource (lib "eagle-import") (part "1,6/0,8"))
    )
    (comp (ref "PAD38")
      (value "1,6/0,8")
      (footprint "eagle-import:1,6_0,8")
      (libsource (lib "eagle-import") (part "1,6/0,8"))
    )
    (comp (ref "PAD39")
      (value "1,6/0,8")
      (footprint "eagle-import:1,6_0,8")
      (libsource (lib "eagle-import") (part "1,6/0,8"))
    )
    (comp (ref "PAD40")
      (value "1,6/0,8")
      (footprint "eagle-import:1,6_0,8")
      (libsource (lib "eagle-import") (part "1,6/0,8"))
    )
    (comp (ref "PAD41")
      (value "1,6/0,8")
      (footprint "eagle-import:1,6_0,8")
      (libsource (lib "eagle-import") (part "1,6/0,8"))
    )
    (comp (ref "R1")
      (value "180")
      (footprint "eagle-import:0207_10")
      (libsource (lib "eagle-import") (part "R-US_0207/10"))
    )
    (comp (ref "R2")
      (value "180")
      (footprint "eagle-import:0207_10")
      (libsource (lib "eagle-import") (part "R-US_0207/10"))
    )
    (comp (ref "R3")
      (value "180")
      (footprint "eagle-import:0207_10")
      (libsource (lib "eagle-import") (part "R-US_0207/10"))
    )
    (comp (ref "R4")
      (value "180")
      (footprint "eagle-import:0207_10")
      (libsource (lib "eagle-import") (part "R-US_0207/10"))
    )
    (comp (ref "R5")
      (value "180")
      (footprint "eagle-import:0207_10")
      (libsource (lib "eagle-import") (part "R-US_0207/10"))
    )
    (comp (ref "R6")
      (value "180")
      (footprint "eagle-import:0207_10")
      (libsource (lib "eagle-import") (part "R-US_0207/10"))
    )
    (comp (ref "R8")
      (value "180")
      (footprint "eagle-import:0207_10")
      (libsource (lib "eagle-import") (part "R-US_0207/10"))
    )
    (comp (ref "R10")
      (value "390")
      (footprint "eagle-import:0207_10")
      (libsource (lib "eagle-import") (part "R-US_0207/10"))
    )
    (comp (ref "R11")
      (value "390")
      (footprint "eagle-import:0207_10")
      (libsource (lib "eagle-import") (part "R-US_0207/10"))
    )
    (comp (ref "R12")
      (value "390")
      (footprint "eagle-import:0207_10")
      (libsource (lib "eagle-import") (part "R-US_0207/10"))
    )
    (comp (ref "R13")
      (value "390")
      (footprint "eagle-import:0207_10")
      (libsource (lib "eagle-import") (part "R-US_0207/10"))
    )
    (comp (ref "R14")
      (value "390")
      (footprint "eagle-import:0207_10")
      (libsource (lib "eagle-import") (part "R-US_0207/10"))
    )
    (comp (ref "R15")
      (value "390")
      (footprint "eagle-import:0207_10")
      (libsource (lib "eagle-import") (part "R-US_0207/10"))
    )
    (comp (ref "R17")
      (value "390")
      (footprint "eagle-import:0207_10")
      (libsource (lib "eagle-import") (part "R-US_0207/10"))
    )
    (comp (ref "R18")
      (value "10K")
      (footprint "eagle-import:0207_10")
      (libsource (lib "eagle-import") (part "R-US_0207/10"))
    )
  )
  (nets
    (net (code "1") (name "8{slash}12") (class "Default")
      (node (ref "E2") (pin "9") (pinfunction "Q_9") (pintype "output"))
      (node (ref "E5") (pin "13") (pinfunction "I1_13") (pintype "input"))
      (node (ref "E8") (pin "4") (pinfunction "I1_4") (pintype "input"))
    )
    (net (code "2") (name "8{slash}~{12}") (class "Default")
      (node (ref "E10") (pin "13") (pinfunction "I2_13") (pintype "input"))
      (node (ref "E2") (pin "8") (pinfunction "~{Q}_8") (pintype "output"))
      (node (ref "E24") (pin "1") (pinfunction "I0_1") (pintype "input"))
      (node (ref "E5") (pin "2") (pinfunction "I1_2") (pintype "input"))
      (node (ref "E8") (pin "1") (pinfunction "I0_1") (pintype "input"))
      (node (ref "IC8") (pin "1") (pinfunction "I0_1") (pintype "input"))
      (node (ref "IC8") (pin "2") (pinfunction "I1_2") (pintype "input"))
    )
    (net (code "3") (name "BAC00") (class "Default")
      (node (ref "D36L1") (pin "D") (pinfunction "4_D") (pintype "bidirectional"))
      (node (ref "D36L2") (pin "D") (pinfunction "4_D") (pintype "bidirectional"))
      (node (ref "E23") (pin "7") (pinfunction "D_7") (pintype "input"))
    )
    (net (code "4") (name "BAC01") (class "Default")
      (node (ref "D36L1") (pin "J") (pinfunction "8_J") (pintype "bidirectional"))
      (node (ref "D36L2") (pin "J") (pinfunction "8_J") (pintype "bidirectional"))
      (node (ref "E23") (pin "6") (pinfunction "C_6") (pintype "input"))
    )
    (net (code "5") (name "BAC02") (class "Default")
      (node (ref "D36L1") (pin "N") (pinfunction "12_N") (pintype "bidirectional"))
      (node (ref "D36L2") (pin "N") (pinfunction "12_N") (pintype "bidirectional"))
      (node (ref "E23") (pin "5") (pinfunction "B_5") (pintype "input"))
    )
    (net (code "6") (name "BAC03") (class "Default")
      (node (ref "D36L1") (pin "T") (pinfunction "16_T") (pintype "bidirectional"))
      (node (ref "D36L2") (pin "T") (pinfunction "16_T") (pintype "bidirectional"))
      (node (ref "E23") (pin "4") (pinfunction "A_4") (pintype "input"))
    )
    (net (code "7") (name "BAC04") (class "Default")
      (node (ref "D36L1") (pin "X") (pinfunction "20_X") (pintype "bidirectional"))
      (node (ref "D36L2") (pin "X") (pinfunction "20_X") (pintype "bidirectional"))
      (node (ref "E21") (pin "7") (pinfunction "D_7") (pintype "input"))
      (node (ref "E6") (pin "2") (pinfunction "D_2") (pintype "input"))
    )
    (net (code "8") (name "BAC05") (class "Default")
      (node (ref "D36L1") (pin "BB") (pinfunction "24_BB") (pintype "bidirectional"))
      (node (ref "D36L2") (pin "BB") (pinfunction "24_BB") (pintype "bidirectional"))
      (node (ref "E2") (pin "12") (pinfunction "D_12") (pintype "input"))
      (node (ref "E21") (pin "6") (pinfunction "C_6") (pintype "input"))
    )
    (net (code "9") (name "BAC06") (class "Default")
      (node (ref "D36L1") (pin "FF") (pinfunction "28_FF") (pintype "bidirectional"))
      (node (ref "D36L2") (pin "FF") (pinfunction "28_FF") (pintype "bidirectional"))
      (node (ref "E21") (pin "5") (pinfunction "B_5") (pintype "input"))
    )
    (net (code "10") (name "BAC07") (class "Default")
      (node (ref "D36L1") (pin "LL") (pinfunction "32_LL") (pintype "bidirectional"))
      (node (ref "D36L2") (pin "LL") (pinfunction "32_LL") (pintype "bidirectional"))
      (node (ref "E21") (pin "4") (pinfunction "A_4") (pintype "input"))
    )
    (net (code "11") (name "BAC08") (class "Default")
      (node (ref "D36L1") (pin "RR") (pinfunction "36_RR") (pintype "bidirectional"))
      (node (ref "D36L2") (pin "RR") (pinfunction "36_RR") (pintype "bidirectional"))
      (node (ref "E22") (pin "7") (pinfunction "D_7") (pintype "input"))
    )
    (net (code "12") (name "BAC09") (class "Default")
      (node (ref "D36L1") (pin "F") (pinfunction "6_F") (pintype "bidirectional"))
      (node (ref "D36L2") (pin "F") (pinfunction "6_F") (pintype "bidirectional"))
      (node (ref "E22") (pin "6") (pinfunction "C_6") (pintype "input"))
    )
    (net (code "13") (name "BAC10") (class "Default")
      (node (ref "D36L1") (pin "L") (pinfunction "10_L") (pintype "bidirectional"))
      (node (ref "D36L2") (pin "L") (pinfunction "10_L") (pintype "bidirectional"))
      (node (ref "E22") (pin "5") (pinfunction "B_5") (pintype "input"))
    )
    (net (code "14") (name "BAC11") (class "Default")
      (node (ref "D36L1") (pin "R") (pinfunction "14_R") (pintype "bidirectional"))
      (node (ref "D36L2") (pin "R") (pinfunction "14_R") (pintype "bidirectional"))
      (node (ref "E22") (pin "4") (pinfunction "A_4") (pintype "input"))
      (node (ref "E30") (pin "2") (pinfunction "D_2") (pintype "input"))
    )
    (net (code "15") (name "BINIT") (class "Default")
      (node (ref "D36L1") (pin "TT") (pinfunction "38_TT") (pintype "bidirectional"))
      (node (ref "D36L2") (pin "TT") (pinfunction "38_TT") (pintype "bidirectional"))
      (node (ref "E1") (pin "3") (pinfunction "I0_3") (pintype "input"))
      (node (ref "LASTDEV") (pin "2") (pinfunction "2_2") (pintype "passive"))
    )
    (net (code "16") (name "BIOP1") (class "Default")
      (node (ref "D36L1") (pin "V") (pinfunction "18_V") (pintype "bidirectional"))
      (node (ref "D36L2") (pin "V") (pinfunction "18_V") (pintype "bidirectional"))
      (node (ref "E11") (pin "6") (pinfunction "G1_6") (pintype "input"))
      (node (ref "LASTDEV") (pin "7") (pinfunction "7_7") (pintype "passive"))
    )
    (net (code "17") (name "BIOP2") (class "Default")
      (node (ref "D36L1") (pin "Z") (pinfunction "22_Z") (pintype "bidirectional"))
      (node (ref "D36L2") (pin "Z") (pinfunction "22_Z") (pintype "bidirectional"))
      (node (ref "E12") (pin "6") (pinfunction "G1_6") (pintype "input"))
      (node (ref "LASTDEV") (pin "6") (pinfunction "6_6") (pintype "passive"))
    )
    (net (code "18") (name "BIOP4") (class "Default")
      (node (ref "D36L1") (pin "DD") (pinfunction "26_DD") (pintype "bidirectional"))
      (node (ref "D36L2") (pin "DD") (pinfunction "26_DD") (pintype "bidirectional"))
      (node (ref "E13") (pin "6") (pinfunction "G1_6") (pintype "input"))
      (node (ref "LASTDEV") (pin "5") (pinfunction "5_5") (pintype "passive"))
    )
    (net (code "19") (name "BMB00") (class "Default")
      (node (ref "D35L1") (pin "D") (pinfunction "4_D") (pintype "bidirectional"))
      (node (ref "D35L2") (pin "D") (pinfunction "4_D") (pintype "bidirectional"))
    )
    (net (code "20") (name "BMB01") (class "Default")
      (node (ref "D35L1") (pin "J") (pinfunction "8_J") (pintype "bidirectional"))
      (node (ref "D35L2") (pin "J") (pinfunction "8_J") (pintype "bidirectional"))
    )
    (net (code "21") (name "BMB02") (class "Default")
      (node (ref "D35L1") (pin "N") (pinfunction "12_N") (pintype "bidirectional"))
      (node (ref "D35L2") (pin "N") (pinfunction "12_N") (pintype "bidirectional"))
    )
    (net (code "22") (name "BMB03") (class "Default")
      (node (ref "D35L1") (pin "X") (pinfunction "20_X") (pintype "bidirectional"))
      (node (ref "D35L2") (pin "X") (pinfunction "20_X") (pintype "bidirectional"))
      (node (ref "E1") (pin "13") (pinfunction "I2_13") (pintype "input"))
    )
    (net (code "23") (name "BMB04") (class "Default")
      (node (ref "D35L1") (pin "FF") (pinfunction "28_FF") (pintype "bidirectional"))
      (node (ref "D35L2") (pin "FF") (pinfunction "28_FF") (pintype "bidirectional"))
      (node (ref "E1") (pin "2") (pinfunction "I1_2") (pintype "input"))
    )
    (net (code "24") (name "BMB05") (class "Default")
      (node (ref "D35L1") (pin "RR") (pinfunction "36_RR") (pintype "bidirectional"))
      (node (ref "D35L2") (pin "RR") (pinfunction "36_RR") (pintype "bidirectional"))
      (node (ref "E1") (pin "1") (pinfunction "I0_1") (pintype "input"))
    )
    (net (code "25") (name "BMB06") (class "Default")
      (node (ref "D35L1") (pin "L") (pinfunction "10_L") (pintype "bidirectional"))
      (node (ref "D35L2") (pin "L") (pinfunction "10_L") (pintype "bidirectional"))
      (node (ref "E14") (pin "3") (pinfunction "C_3") (pintype "input"))
    )
    (net (code "26") (name "BMB07") (class "Default")
      (node (ref "D35L1") (pin "V") (pinfunction "18_V") (pintype "bidirectional"))
      (node (ref "D35L2") (pin "V") (pinfunction "18_V") (pintype "bidirectional"))
      (node (ref "E14") (pin "2") (pinfunction "B_2") (pintype "input"))
    )
    (net (code "27") (name "BMB08") (class "Default")
      (node (ref "D35L1") (pin "DD") (pinfunction "26_DD") (pintype "bidirectional"))
      (node (ref "D35L2") (pin "DD") (pinfunction "26_DD") (pintype "bidirectional"))
      (node (ref "E14") (pin "1") (pinfunction "A_1") (pintype "input"))
    )
    (net (code "28") (name "BMB09") (class "Default")
      (node (ref "D35L1") (pin "JJ") (pinfunction "30_JJ") (pintype "bidirectional"))
      (node (ref "D35L2") (pin "JJ") (pinfunction "30_JJ") (pintype "bidirectional"))
      (node (ref "E11") (pin "3") (pinfunction "C_3") (pintype "input"))
      (node (ref "E12") (pin "3") (pinfunction "C_3") (pintype "input"))
      (node (ref "E13") (pin "3") (pinfunction "C_3") (pintype "input"))
    )
    (net (code "29") (name "BMB10") (class "Default")
      (node (ref "D35L1") (pin "NN") (pinfunction "34_NN") (pintype "bidirectional"))
      (node (ref "D35L2") (pin "NN") (pinfunction "34_NN") (pintype "bidirectional"))
      (node (ref "E11") (pin "2") (pinfunction "B_2") (pintype "input"))
      (node (ref "E12") (pin "2") (pinfunction "B_2") (pintype "input"))
      (node (ref "E13") (pin "2") (pinfunction "B_2") (pintype "input"))
    )
    (net (code "30") (name "BMB11") (class "Default")
      (node (ref "D35L1") (pin "TT") (pinfunction "38_TT") (pintype "bidirectional"))
      (node (ref "D35L2") (pin "TT") (pinfunction "38_TT") (pintype "bidirectional"))
      (node (ref "E11") (pin "1") (pinfunction "A_1") (pintype "input"))
      (node (ref "E12") (pin "1") (pinfunction "A_1") (pintype "input"))
      (node (ref "E13") (pin "1") (pinfunction "A_1") (pintype "input"))
    )
    (net (code "31") (name "BTS1") (class "Default")
      (node (ref "D36L1") (pin "NN") (pinfunction "34_NN") (pintype "bidirectional"))
      (node (ref "D36L2") (pin "NN") (pinfunction "34_NN") (pintype "bidirectional"))
      (node (ref "E16") (pin "13") (pinfunction "C12_13") (pintype "input"))
      (node (ref "E16") (pin "4") (pinfunction "C34_4") (pintype "input"))
      (node (ref "LASTDEV") (pin "3") (pinfunction "3_3") (pintype "passive"))
    )
    (net (code "32") (name "BTS3") (class "Default")
      (node (ref "D36L1") (pin "JJ") (pinfunction "30_JJ") (pintype "bidirectional"))
      (node (ref "D36L2") (pin "JJ") (pinfunction "30_JJ") (pintype "bidirectional"))
      (node (ref "LASTDEV") (pin "4") (pinfunction "4_4") (pintype "passive"))
    )
    (net (code "33") (name "CLK_BUF") (class "Default")
      (node (ref "E21") (pin "10") (pinfunction "CLK_10") (pintype "input"))
      (node (ref "E22") (pin "10") (pinfunction "CLK_10") (pintype "input"))
      (node (ref "E23") (pin "10") (pinfunction "CLK_10") (pintype "input"))
      (node (ref "E4") (pin "2") (pinfunction "CLK_2") (pintype "input"))
      (node (ref "E5") (pin "6") (pinfunction "O_6") (pintype "output"))
    )
    (net (code "34") (name "DONE") (class "Default")
      (node (ref "E20") (pin "13") (pinfunction "I1_13") (pintype "input"))
      (node (ref "E25") (pin "3") (pinfunction "I_3") (pintype "input"))
      (node (ref "E31") (pin "4") (pinfunction "I2_4") (pintype "input"))
      (node (ref "E32") (pin "11") (pinfunction "I2_11") (pintype "input"))
      (node (ref "E36") (pin "10") (pinfunction "O_10") (pintype "output"))
      (node (ref "E6") (pin "11") (pinfunction "CLK_11") (pintype "input"))
    )
    (net (code "35") (name "DONE_FF") (class "Default")
      (node (ref "E16") (pin "10") (pinfunction "Q3_10") (pintype "output"))
      (node (ref "IC10") (pin "6") (pinfunction "I0_6") (pintype "input"))
    )
    (net (code "36") (name "DONE_SKIP") (class "Default")
      (node (ref "E18") (pin "10") (pinfunction "O_10") (pintype "output"))
      (node (ref "E20") (pin "5") (pinfunction "I1_5") (pintype "input"))
      (node (ref "E26") (pin "9") (pinfunction "I1_9") (pintype "input"))
    )
    (net (code "37") (name "ERROR") (class "Default")
      (node (ref "E19") (pin "11") (pinfunction "CLK_11") (pintype "input"))
      (node (ref "E36") (pin "1") (pinfunction "O_1") (pintype "output"))
    )
    (net (code "38") (name "ERR_SKIP") (class "Default")
      (node (ref "E18") (pin "4") (pinfunction "O_4") (pintype "output"))
      (node (ref "E20") (pin "4") (pinfunction "I0_4") (pintype "input"))
      (node (ref "E26") (pin "6") (pinfunction "I1_6") (pintype "input"))
    )
    (net (code "39") (name "GND") (class "Default")
      (node (ref "C1") (pin "2") (pinfunction "2_2") (pintype "passive"))
      (node (ref "C10") (pin "2") (pinfunction "2_2") (pintype "passive"))
      (node (ref "C11") (pin "2") (pinfunction "2_2") (pintype "passive"))
      (node (ref "C12") (pin "2") (pinfunction "2_2") (pintype "passive"))
      (node (ref "C13") (pin "2") (pinfunction "2_2") (pintype "passive"))
      (node (ref "C14") (pin "2") (pinfunction "2_2") (pintype "passive"))
      (node (ref "C15") (pin "2") (pinfunction "2_2") (pintype "passive"))
      (node (ref "C16") (pin "2") (pinfunction "2_2") (pintype "passive"))
      (node (ref "C17") (pin "2") (pinfunction "2_2") (pintype "passive"))
      (node (ref "C18") (pin "2") (pinfunction "2_2") (pintype "passive"))
      (node (ref "C19") (pin "2") (pinfunction "2_2") (pintype "passive"))
      (node (ref "C2") (pin "2") (pinfunction "2_2") (pintype "passive"))
      (node (ref "C20") (pin "2") (pinfunction "2_2") (pintype "passive"))
      (node (ref "C21") (pin "2") (pinfunction "2_2") (pintype "passive"))
      (node (ref "C22") (pin "2") (pinfunction "2_2") (pintype "passive"))
      (node (ref "C23") (pin "2") (pinfunction "2_2") (pintype "passive"))
      (node (ref "C24") (pin "2") (pinfunction "2_2") (pintype "passive"))
      (node (ref "C25") (pin "2") (pinfunction "2_2") (pintype "passive"))
      (node (ref "C26") (pin "2") (pinfunction "2_2") (pintype "passive"))
      (node (ref "C27") (pin "2") (pinfunction "2_2") (pintype "passive"))
      (node (ref "C28") (pin "2") (pinfunction "2_2") (pintype "passive"))
      (node (ref "C29") (pin "2") (pinfunction "2_2") (pintype "passive"))
      (node (ref "C3") (pin "2") (pinfunction "2_2") (pintype "passive"))
      (node (ref "C30") (pin "2") (pinfunction "2_2") (pintype "passive"))
      (node (ref "C31") (pin "2") (pinfunction "2_2") (pintype "passive"))
      (node (ref "C32") (pin "2") (pinfunction "2_2") (pintype "passive"))
      (node (ref "C33") (pin "2") (pinfunction "2_2") (pintype "passive"))
      (node (ref "C34") (pin "2") (pinfunction "2_2") (pintype "passive"))
      (node (ref "C35") (pin "2") (pinfunction "2_2") (pintype "passive"))
      (node (ref "C36") (pin "2") (pinfunction "2_2") (pintype "passive"))
      (node (ref "C37") (pin "2") (pinfunction "2_2") (pintype "passive"))
      (node (ref "C38") (pin "2") (pinfunction "2_2") (pintype "passive"))
      (node (ref "C39") (pin "2") (pinfunction "2_2") (pintype "passive"))
      (node (ref "C4") (pin "2") (pinfunction "2_2") (pintype "passive"))
      (node (ref "C40") (pin "-") (pinfunction "-_-") (pintype "passive"))
      (node (ref "C5") (pin "2") (pinfunction "2_2") (pintype "passive"))
      (node (ref "C6") (pin "2") (pinfunction "2_2") (pintype "passive"))
      (node (ref "C7") (pin "2") (pinfunction "2_2") (pintype "passive"))
      (node (ref "C8") (pin "2") (pinfunction "2_2") (pintype "passive"))
      (node (ref "C9") (pin "2") (pinfunction "2_2") (pintype "passive"))
      (node (ref "D34L1") (pin "A") (pinfunction "1_A") (pintype "bidirectional"))
      (node (ref "D34L1") (pin "AA") (pinfunction "23_AA") (pintype "bidirectional"))
      (node (ref "D34L1") (pin "C") (pinfunction "3_C") (pintype "bidirectional"))
      (node (ref "D34L1") (pin "CC") (pinfunction "25_CC") (pintype "bidirectional"))
      (node (ref "D34L1") (pin "E") (pinfunction "5_E") (pintype "bidirectional"))
      (node (ref "D34L1") (pin "EE") (pinfunction "27_EE") (pintype "bidirectional"))
      (node (ref "D34L1") (pin "H") (pinfunction "7_H") (pintype "bidirectional"))
      (node (ref "D34L1") (pin "HH") (pinfunction "29_HH") (pintype "bidirectional"))
      (node (ref "D34L1") (pin "K") (pinfunction "9_K") (pintype "bidirectional"))
      (node (ref "D34L1") (pin "KK") (pinfunction "31_KK") (pintype "bidirectional"))
      (node (ref "D34L1") (pin "M") (pinfunction "11_M") (pintype "bidirectional"))
      (node (ref "D34L1") (pin "MM") (pinfunction "33_MM") (pintype "bidirectional"))
      (node (ref "D34L1") (pin "P") (pinfunction "13_P") (pintype "bidirectional"))
      (node (ref "D34L1") (pin "PP") (pinfunction "35_PP") (pintype "bidirectional"))
      (node (ref "D34L1") (pin "S") (pinfunction "15_S") (pintype "bidirectional"))
      (node (ref "D34L1") (pin "SS") (pinfunction "37_SS") (pintype "bidirectional"))
      (node (ref "D34L1") (pin "U") (pinfunction "17_U") (pintype "bidirectional"))
      (node (ref "D34L1") (pin "UU") (pinfunction "39_UU") (pintype "bidirectional"))
      (node (ref "D34L1") (pin "W") (pinfunction "19_W") (pintype "bidirectional"))
      (node (ref "D34L1") (pin "Y") (pinfunction "21_Y") (pintype "bidirectional"))
      (node (ref "D34L2") (pin "A") (pinfunction "1_A") (pintype "bidirectional"))
      (node (ref "D34L2") (pin "AA") (pinfunction "23_AA") (pintype "bidirectional"))
      (node (ref "D34L2") (pin "C") (pinfunction "3_C") (pintype "bidirectional"))
      (node (ref "D34L2") (pin "CC") (pinfunction "25_CC") (pintype "bidirectional"))
      (node (ref "D34L2") (pin "E") (pinfunction "5_E") (pintype "bidirectional"))
      (node (ref "D34L2") (pin "EE") (pinfunction "27_EE") (pintype "bidirectional"))
      (node (ref "D34L2") (pin "H") (pinfunction "7_H") (pintype "bidirectional"))
      (node (ref "D34L2") (pin "HH") (pinfunction "29_HH") (pintype "bidirectional"))
      (node (ref "D34L2") (pin "K") (pinfunction "9_K") (pintype "bidirectional"))
      (node (ref "D34L2") (pin "KK") (pinfunction "31_KK") (pintype "bidirectional"))
      (node (ref "D34L2") (pin "M") (pinfunction "11_M") (pintype "bidirectional"))
      (node (ref "D34L2") (pin "MM") (pinfunction "33_MM") (pintype "bidirectional"))
      (node (ref "D34L2") (pin "P") (pinfunction "13_P") (pintype "bidirectional"))
      (node (ref "D34L2") (pin "PP") (pinfunction "35_PP") (pintype "bidirectional"))
      (node (ref "D34L2") (pin "S") (pinfunction "15_S") (pintype "bidirectional"))
      (node (ref "D34L2") (pin "SS") (pinfunction "37_SS") (pintype "bidirectional"))
      (node (ref "D34L2") (pin "U") (pinfunction "17_U") (pintype "bidirectional"))
      (node (ref "D34L2") (pin "UU") (pinfunction "39_UU") (pintype "bidirectional"))
      (node (ref "D34L2") (pin "W") (pinfunction "19_W") (pintype "bidirectional"))
      (node (ref "D34L2") (pin "Y") (pinfunction "21_Y") (pintype "bidirectional"))
      (node (ref "D35L1") (pin "A") (pinfunction "1_A") (pintype "bidirectional"))
      (node (ref "D35L1") (pin "AA") (pinfunction "23_AA") (pintype "bidirectional"))
      (node (ref "D35L1") (pin "C") (pinfunction "3_C") (pintype "bidirectional"))
      (node (ref "D35L1") (pin "CC") (pinfunction "25_CC") (pintype "bidirectional"))
      (node (ref "D35L1") (pin "E") (pinfunction "5_E") (pintype "bidirectional"))
      (node (ref "D35L1") (pin "EE") (pinfunction "27_EE") (pintype "bidirectional"))
      (node (ref "D35L1") (pin "H") (pinfunction "7_H") (pintype "bidirectional"))
      (node (ref "D35L1") (pin "HH") (pinfunction "29_HH") (pintype "bidirectional"))
      (node (ref "D35L1") (pin "K") (pinfunction "9_K") (pintype "bidirectional"))
      (node (ref "D35L1") (pin "KK") (pinfunction "31_KK") (pintype "bidirectional"))
      (node (ref "D35L1") (pin "M") (pinfunction "11_M") (pintype "bidirectional"))
      (node (ref "D35L1") (pin "MM") (pinfunction "33_MM") (pintype "bidirectional"))
      (node (ref "D35L1") (pin "P") (pinfunction "13_P") (pintype "bidirectional"))
      (node (ref "D35L1") (pin "PP") (pinfunction "35_PP") (pintype "bidirectional"))
      (node (ref "D35L1") (pin "S") (pinfunction "15_S") (pintype "bidirectional"))
      (node (ref "D35L1") (pin "SS") (pinfunction "37_SS") (pintype "bidirectional"))
      (node (ref "D35L1") (pin "U") (pinfunction "17_U") (pintype "bidirectional"))
      (node (ref "D35L1") (pin "UU") (pinfunction "39_UU") (pintype "bidirectional"))
      (node (ref "D35L1") (pin "W") (pinfunction "19_W") (pintype "bidirectional"))
      (node (ref "D35L1") (pin "Y") (pinfunction "21_Y") (pintype "bidirectional"))
      (node (ref "D35L2") (pin "A") (pinfunction "1_A") (pintype "bidirectional"))
      (node (ref "D35L2") (pin "AA") (pinfunction "23_AA") (pintype "bidirectional"))
      (node (ref "D35L2") (pin "C") (pinfunction "3_C") (pintype "bidirectional"))
      (node (ref "D35L2") (pin "CC") (pinfunction "25_CC") (pintype "bidirectional"))
      (node (ref "D35L2") (pin "E") (pinfunction "5_E") (pintype "bidirectional"))
      (node (ref "D35L2") (pin "EE") (pinfunction "27_EE") (pintype "bidirectional"))
      (node (ref "D35L2") (pin "H") (pinfunction "7_H") (pintype "bidirectional"))
      (node (ref "D35L2") (pin "HH") (pinfunction "29_HH") (pintype "bidirectional"))
      (node (ref "D35L2") (pin "K") (pinfunction "9_K") (pintype "bidirectional"))
      (node (ref "D35L2") (pin "KK") (pinfunction "31_KK") (pintype "bidirectional"))
      (node (ref "D35L2") (pin "M") (pinfunction "11_M") (pintype "bidirectional"))
      (node (ref "D35L2") (pin "MM") (pinfunction "33_MM") (pintype "bidirectional"))
      (node (ref "D35L2") (pin "P") (pinfunction "13_P") (pintype "bidirectional"))
      (node (ref "D35L2") (pin "PP") (pinfunction "35_PP") (pintype "bidirectional"))
      (node (ref "D35L2") (pin "S") (pinfunction "15_S") (pintype "bidirectional"))
      (node (ref "D35L2") (pin "SS") (pinfunction "37_SS") (pintype "bidirectional"))
      (node (ref "D35L2") (pin "U") (pinfunction "17_U") (pintype "bidirectional"))
      (node (ref "D35L2") (pin "UU") (pinfunction "39_UU") (pintype "bidirectional"))
      (node (ref "D35L2") (pin "W") (pinfunction "19_W") (pintype "bidirectional"))
      (node (ref "D35L2") (pin "Y") (pinfunction "21_Y") (pintype "bidirectional"))
      (node (ref "D36L1") (pin "A") (pinfunction "1_A") (pintype "bidirectional"))
      (node (ref "D36L1") (pin "AA") (pinfunction "23_AA") (pintype "bidirectional"))
      (node (ref "D36L1") (pin "C") (pinfunction "3_C") (pintype "bidirectional"))
      (node (ref "D36L1") (pin "CC") (pinfunction "25_CC") (pintype "bidirectional"))
      (node (ref "D36L1") (pin "E") (pinfunction "5_E") (pintype "bidirectional"))
      (node (ref "D36L1") (pin "EE") (pinfunction "27_EE") (pintype "bidirectional"))
      (node (ref "D36L1") (pin "H") (pinfunction "7_H") (pintype "bidirectional"))
      (node (ref "D36L1") (pin "HH") (pinfunction "29_HH") (pintype "bidirectional"))
      (node (ref "D36L1") (pin "K") (pinfunction "9_K") (pintype "bidirectional"))
      (node (ref "D36L1") (pin "KK") (pinfunction "31_KK") (pintype "bidirectional"))
      (node (ref "D36L1") (pin "M") (pinfunction "11_M") (pintype "bidirectional"))
      (node (ref "D36L1") (pin "MM") (pinfunction "33_MM") (pintype "bidirectional"))
      (node (ref "D36L1") (pin "P") (pinfunction "13_P") (pintype "bidirectional"))
      (node (ref "D36L1") (pin "PP") (pinfunction "35_PP") (pintype "bidirectional"))
      (node (ref "D36L1") (pin "S") (pinfunction "15_S") (pintype "bidirectional"))
      (node (ref "D36L1") (pin "SS") (pinfunction "37_SS") (pintype "bidirectional"))
      (node (ref "D36L1") (pin "U") (pinfunction "17_U") (pintype "bidirectional"))
      (node (ref "D36L1") (pin "UU") (pinfunction "39_UU") (pintype "bidirectional"))
      (node (ref "D36L1") (pin "W") (pinfunction "19_W") (pintype "bidirectional"))
      (node (ref "D36L1") (pin "Y") (pinfunction "21_Y") (pintype "bidirectional"))
      (node (ref "D36L2") (pin "A") (pinfunction "1_A") (pintype "bidirectional"))
      (node (ref "D36L2") (pin "AA") (pinfunction "23_AA") (pintype "bidirectional"))
      (node (ref "D36L2") (pin "C") (pinfunction "3_C") (pintype "bidirectional"))
      (node (ref "D36L2") (pin "CC") (pinfunction "25_CC") (pintype "bidirectional"))
      (node (ref "D36L2") (pin "E") (pinfunction "5_E") (pintype "bidirectional"))
      (node (ref "D36L2") (pin "EE") (pinfunction "27_EE") (pintype "bidirectional"))
      (node (ref "D36L2") (pin "H") (pinfunction "7_H") (pintype "bidirectional"))
      (node (ref "D36L2") (pin "HH") (pinfunction "29_HH") (pintype "bidirectional"))
      (node (ref "D36L2") (pin "K") (pinfunction "9_K") (pintype "bidirectional"))
      (node (ref "D36L2") (pin "KK") (pinfunction "31_KK") (pintype "bidirectional"))
      (node (ref "D36L2") (pin "M") (pinfunction "11_M") (pintype "bidirectional"))
      (node (ref "D36L2") (pin "MM") (pinfunction "33_MM") (pintype "bidirectional"))
      (node (ref "D36L2") (pin "P") (pinfunction "13_P") (pintype "bidirectional"))
      (node (ref "D36L2") (pin "PP") (pinfunction "35_PP") (pintype "bidirectional"))
      (node (ref "D36L2") (pin "S") (pinfunction "15_S") (pintype "bidirectional"))
      (node (ref "D36L2") (pin "SS") (pinfunction "37_SS") (pintype "bidirectional"))
      (node (ref "D36L2") (pin "U") (pinfunction "17_U") (pintype "bidirectional"))
      (node (ref "D36L2") (pin "UU") (pinfunction "39_UU") (pintype "bidirectional"))
      (node (ref "D36L2") (pin "W") (pinfunction "19_W") (pintype "bidirectional"))
      (node (ref "D36L2") (pin "Y") (pinfunction "21_Y") (pintype "bidirectional"))
      (node (ref "DRIVE") (pin "A") (pinfunction "1_A") (pintype "bidirectional"))
      (node (ref "DRIVE") (pin "AA") (pinfunction "23_AA") (pintype "bidirectional"))
      (node (ref "DRIVE") (pin "B") (pinfunction "2_B") (pintype "bidirectional"))
      (node (ref "DRIVE") (pin "C") (pinfunction "3_C") (pintype "bidirectional"))
      (node (ref "DRIVE") (pin "CC") (pinfunction "25_CC") (pintype "bidirectional"))
      (node (ref "DRIVE") (pin "DD") (pinfunction "26_DD") (pintype "bidirectional"))
      (node (ref "DRIVE") (pin "E") (pinfunction "5_E") (pintype "bidirectional"))
      (node (ref "DRIVE") (pin "EE") (pinfunction "27_EE") (pintype "bidirectional"))
      (node (ref "DRIVE") (pin "F") (pinfunction "6_F") (pintype "bidirectional"))
      (node (ref "DRIVE") (pin "H") (pinfunction "7_H") (pintype "bidirectional"))
      (node (ref "DRIVE") (pin "HH") (pinfunction "29_HH") (pintype "bidirectional"))
      (node (ref "DRIVE") (pin "JJ") (pinfunction "30_JJ") (pintype "bidirectional"))
      (node (ref "DRIVE") (pin "K") (pinfunction "9_K") (pintype "bidirectional"))
      (node (ref "DRIVE") (pin "KK") (pinfunction "31_KK") (pintype "bidirectional"))
      (node (ref "DRIVE") (pin "L") (pinfunction "10_L") (pintype "bidirectional"))
      (node (ref "DRIVE") (pin "M") (pinfunction "11_M") (pintype "bidirectional"))
      (node (ref "DRIVE") (pin "MM") (pinfunction "33_MM") (pintype "bidirectional"))
      (node (ref "DRIVE") (pin "NN") (pinfunction "34_NN") (pintype "bidirectional"))
      (node (ref "DRIVE") (pin "P") (pinfunction "13_P") (pintype "bidirectional"))
      (node (ref "DRIVE") (pin "PP") (pinfunction "35_PP") (pintype "bidirectional"))
      (node (ref "DRIVE") (pin "R") (pinfunction "14_R") (pintype "bidirectional"))
      (node (ref "DRIVE") (pin "S") (pinfunction "15_S") (pintype "bidirectional"))
      (node (ref "DRIVE") (pin "SS") (pinfunction "37_SS") (pintype "bidirectional"))
      (node (ref "DRIVE") (pin "TT") (pinfunction "38_TT") (pintype "bidirectional"))
      (node (ref "DRIVE") (pin "U") (pinfunction "17_U") (pintype "bidirectional"))
      (node (ref "DRIVE") (pin "UU") (pinfunction "39_UU") (pintype "bidirectional"))
      (node (ref "DRIVE") (pin "V") (pinfunction "18_V") (pintype "bidirectional"))
      (node (ref "DRIVE") (pin "VV") (pinfunction "40_VV") (pintype "bidirectional"))
      (node (ref "DRIVE") (pin "W") (pinfunction "19_W") (pintype "bidirectional"))
      (node (ref "DRIVE") (pin "Y") (pinfunction "21_Y") (pintype "bidirectional"))
      (node (ref "DRIVE") (pin "Z") (pinfunction "22_Z") (pintype "bidirectional"))
      (node (ref "E11") (pin "5") (pinfunction "G2B_5") (pintype "input"))
      (node (ref "E12") (pin "5") (pinfunction "G2B_5") (pintype "input"))
      (node (ref "E13") (pin "5") (pinfunction "G2B_5") (pintype "input"))
      (node (ref "E17") (pin "16") (pinfunction "K_16") (pintype "input"))
      (node (ref "E2") (pin "2") (pinfunction "D_2") (pintype "input"))
      (node (ref "E4") (pin "6") (pinfunction "D_6") (pintype "input"))
      (node (ref "LASTDEV") (pin "1") (pinfunction "1_1") (pintype "passive"))
      (node (ref "R10") (pin "1") (pinfunction "1_1") (pintype "passive"))
      (node (ref "R11") (pin "1") (pinfunction "1_1") (pintype "passive"))
      (node (ref "R12") (pin "1") (pinfunction "1_1") (pintype "passive"))
      (node (ref "R13") (pin "1") (pinfunction "1_1") (pintype "passive"))
      (node (ref "R14") (pin "1") (pinfunction "1_1") (pintype "passive"))
      (node (ref "R15") (pin "1") (pinfunction "1_1") (pintype "passive"))
      (node (ref "R16") (pin "1") (pinfunction "1_1") (pintype "passive"))
      (node (ref "R17") (pin "1") (pinfunction "1_1") (pintype "passive"))
      (node (ref "SL1") (pin "2") (pinfunction "S_2") (pintype "passive"))
      (node (ref "SL1") (pin "3") (pinfunction "S_3") (pintype "passive"))
    )
    (net (code "40") (name "INIT") (class "Default")
      (node (ref "E1") (pin "8") (pinfunction "O_8") (pintype "output"))
      (node (ref "E15") (pin "4") (pinfunction "I0_4") (pintype "input"))
      (node (ref "E15") (pin "5") (pinfunction "I1_5") (pintype "input"))
      (node (ref "E18") (pin "12") (pinfunction "I1_12") (pintype "input"))
      (node (ref "E26") (pin "2") (pinfunction "I0_2") (pintype "input"))
      (node (ref "E26") (pin "5") (pinfunction "I0_5") (pintype "input"))
      (node (ref "E26") (pin "8") (pinfunction "I0_8") (pintype "input"))
      (node (ref "IC8") (pin "6") (pinfunction "I0_6") (pintype "input"))
      (node (ref "IC8") (pin "7") (pinfunction "I1_7") (pintype "input"))
    )
    (net (code "41") (name "MAINT") (class "Default")
      (node (ref "E32") (pin "9") (pinfunction "I0_9") (pintype "input"))
      (node (ref "E35") (pin "3") (pinfunction "I1_3") (pintype "input"))
      (node (ref "E35") (pin "6") (pinfunction "I1_6") (pintype "input"))
      (node (ref "E35") (pin "9") (pinfunction "I1_9") (pintype "input"))
      (node (ref "E36") (pin "2") (pinfunction "I0_2") (pintype "input"))
      (node (ref "E36") (pin "6") (pinfunction "I1_6") (pintype "input"))
      (node (ref "E36") (pin "9") (pinfunction "I1_9") (pintype "input"))
      (node (ref "E6") (pin "5") (pinfunction "Q_5") (pintype "output"))
    )
    (net (code "42") (name "MSB8") (class "Default")
      (node (ref "E21") (pin "12") (pinfunction "QD_12") (pintype "output"))
      (node (ref "E23") (pin "2") (pinfunction "J_2") (pintype "input"))
      (node (ref "E23") (pin "3") (pinfunction "K_3") (pintype "input"))
      (node (ref "E8") (pin "5") (pinfunction "I2_5") (pintype "input"))
      (node (ref "IC1") (pin "6") (pinfunction "I0_6") (pintype "input"))
    )
    (net (code "43") (name "MSB12") (class "Default")
      (node (ref "E23") (pin "12") (pinfunction "QD_12") (pintype "output"))
      (node (ref "E8") (pin "2") (pinfunction "I1_2") (pintype "input"))
      (node (ref "IC6") (pin "1") (pinfunction "I0_1") (pintype "input"))
    )
    (net (code "44") (name "Net-(70-P)") (class "Default")
      (node (ref "70") (pin "1") (pinfunction "P_1") (pintype "passive"))
      (node (ref "E14") (pin "15") (pinfunction "Y0_15") (pintype "output"))
    )
    (net (code "45") (name "Net-(71-P)") (class "Default")
      (node (ref "71") (pin "1") (pinfunction "P_1") (pintype "passive"))
      (node (ref "E14") (pin "14") (pinfunction "Y1_14") (pintype "output"))
    )
    (net (code "46") (name "Net-(72-P)") (class "Default")
      (node (ref "72") (pin "1") (pinfunction "P_1") (pintype "passive"))
      (node (ref "E14") (pin "13") (pinfunction "Y2_13") (pintype "output"))
    )
    (net (code "47") (name "Net-(73-P)") (class "Default")
      (node (ref "73") (pin "1") (pinfunction "P_1") (pintype "passive"))
      (node (ref "E14") (pin "12") (pinfunction "Y3_12") (pintype "output"))
    )
    (net (code "48") (name "Net-(74-P)") (class "Default")
      (node (ref "74") (pin "1") (pinfunction "P_1") (pintype "passive"))
      (node (ref "E14") (pin "11") (pinfunction "Y4_11") (pintype "output"))
    )
    (net (code "49") (name "Net-(75-P)") (class "Default")
      (node (ref "75") (pin "1") (pinfunction "P_1") (pintype "passive"))
      (node (ref "E14") (pin "10") (pinfunction "Y5_10") (pintype "output"))
    )
    (net (code "50") (name "Net-(76-P)") (class "Default")
      (node (ref "76") (pin "1") (pinfunction "P_1") (pintype "passive"))
      (node (ref "E14") (pin "9") (pinfunction "Y6_9") (pintype "output"))
    )
    (net (code "51") (name "Net-(77-P)") (class "Default")
      (node (ref "77") (pin "1") (pinfunction "P_1") (pintype "passive"))
      (node (ref "E14") (pin "7") (pinfunction "Y7_7") (pintype "output"))
    )
    (net (code "52") (name "Net-(E1B-O)") (class "Default")
      (node (ref "E1") (pin "10") (pinfunction "I1_10") (pintype "input"))
      (node (ref "E1") (pin "6") (pinfunction "O_6") (pintype "output"))
      (node (ref "E1") (pin "9") (pinfunction "I0_9") (pintype "input"))
      (node (ref "E2") (pin "1") (pinfunction "CLR_1") (pintype "input"))
    )
    (net (code "53") (name "Net-(E1C-I2)") (class "Default")
      (node (ref "E1") (pin "11") (pinfunction "I2_11") (pintype "input"))
      (node (ref "E2") (pin "6") (pinfunction "~{Q}_6") (pintype "output"))
    )
    (net (code "54") (name "Net-(E4A-A)") (class "Default")
      (node (ref "E4") (pin "10") (pinfunction "ENT_10") (pintype "input"))
      (node (ref "E4") (pin "3") (pinfunction "A_3") (pintype "input"))
      (node (ref "E4") (pin "4") (pinfunction "B_4") (pintype "input"))
      (node (ref "E4") (pin "7") (pinfunction "ENP_7") (pintype "input"))
      (node (ref "R19") (pin "2") (pinfunction "2_2") (pintype "passive"))
    )
    (net (code "55") (name "Net-(E4A-C)") (class "Default")
      (node (ref "E4") (pin "5") (pinfunction "C_5") (pintype "input"))
      (node (ref "E5") (pin "3") (pinfunction "O_3") (pintype "output"))
    )
    (net (code "56") (name "Net-(E5A-I0)") (class "Default")
      (node (ref "E5") (pin "1") (pinfunction "I0_1") (pintype "input"))
      (node (ref "E5") (pin "11") (pinfunction "O_11") (pintype "output"))
    )
    (net (code "57") (name "Net-(E8A-O)") (class "Default")
      (node (ref "E8") (pin "11") (pinfunction "I2_11") (pintype "input"))
      (node (ref "E8") (pin "12") (pinfunction "O_12") (pintype "output"))
    )
    (net (code "58") (name "Net-(E8B-O)") (class "Default")
      (node (ref "E8") (pin "6") (pinfunction "O_6") (pintype "output"))
      (node (ref "E8") (pin "9") (pinfunction "I0_9") (pintype "input"))
    )
    (net (code "59") (name "Net-(E10A-I0)") (class "Default")
      (node (ref "E10") (pin "1") (pinfunction "I0_1") (pintype "input"))
      (node (ref "E10") (pin "6") (pinfunction "O_6") (pintype "output"))
    )
    (net (code "60") (name "Net-(E10A-O)") (class "Default")
      (node (ref "E10") (pin "10") (pinfunction "I1_10") (pintype "input"))
      (node (ref "E10") (pin "11") (pinfunction "I2_11") (pintype "input"))
      (node (ref "E10") (pin "12") (pinfunction "O_12") (pintype "output"))
    )
    (net (code "61") (name "Net-(E10C-O)") (class "Default")
      (node (ref "E10") (pin "8") (pinfunction "O_8") (pintype "output"))
      (node (ref "IC7") (pin "1") (pinfunction "I0_1") (pintype "input"))
      (node (ref "IC7") (pin "2") (pinfunction "I1_2") (pintype "input"))
    )
    (net (code "62") (name "Net-(E14A-G2A)") (class "Default")
      (node (ref "E1") (pin "12") (pinfunction "O_12") (pintype "output"))
      (node (ref "E14") (pin "4") (pinfunction "G2A_4") (pintype "input"))
      (node (ref "E14") (pin "5") (pinfunction "G2B_5") (pintype "input"))
    )
    (net (code "63") (name "Net-(E15A-O)") (class "Default")
      (node (ref "E15") (pin "3") (pinfunction "O_3") (pintype "output"))
      (node (ref "E8") (pin "13") (pinfunction "I2_13") (pintype "input"))
      (node (ref "E8") (pin "3") (pinfunction "I0_3") (pintype "input"))
    )
    (net (code "64") (name "Net-(E15C-I0)") (class "Default")
      (node (ref "E15") (pin "9") (pinfunction "I0_9") (pintype "input"))
      (node (ref "E20") (pin "11") (pinfunction "O_11") (pintype "output"))
      (node (ref "E24") (pin "10") (pinfunction "I1_10") (pintype "input"))
    )
    (net (code "65") (name "Net-(E15C-O)") (class "Default")
      (node (ref "E15") (pin "8") (pinfunction "O_8") (pintype "output"))
      (node (ref "E24") (pin "12") (pinfunction "I0_12") (pintype "input"))
    )
    (net (code "66") (name "Net-(E15D-O)") (class "Default")
      (node (ref "E15") (pin "11") (pinfunction "O_11") (pintype "output"))
      (node (ref "E8") (pin "10") (pinfunction "I1_10") (pintype "input"))
    )
    (net (code "67") (name "Net-(E16A-D1)") (class "Default")
      (node (ref "E16") (pin "2") (pinfunction "D1_2") (pintype "input"))
      (node (ref "E19") (pin "5") (pinfunction "Q_5") (pintype "output"))
    )
    (net (code "68") (name "Net-(E16A-D2)") (class "Default")
      (node (ref "E16") (pin "3") (pinfunction "D2_3") (pintype "input"))
      (node (ref "E19") (pin "9") (pinfunction "Q_9") (pintype "output"))
    )
    (net (code "69") (name "Net-(E16A-D3)") (class "Default")
      (node (ref "E16") (pin "6") (pinfunction "D3_6") (pintype "input"))
      (node (ref "E16") (pin "7") (pinfunction "D4_7") (pintype "input"))
      (node (ref "E6") (pin "9") (pinfunction "Q_9") (pintype "output"))
    )
    (net (code "70") (name "Net-(E16A-~{Q1})") (class "Default")
      (node (ref "E16") (pin "1") (pinfunction "~{Q1}_1") (pintype "output"))
      (node (ref "E18") (pin "3") (pinfunction "I1_3") (pintype "input"))
    )
    (net (code "71") (name "Net-(E16A-~{Q2})") (class "Default")
      (node (ref "E16") (pin "14") (pinfunction "~{Q2}_14") (pintype "output"))
      (node (ref "E18") (pin "6") (pinfunction "I1_6") (pintype "input"))
    )
    (net (code "72") (name "Net-(E16A-~{Q3})") (class "Default")
      (node (ref "E16") (pin "11") (pinfunction "~{Q3}_11") (pintype "output"))
      (node (ref "E18") (pin "9") (pinfunction "I1_9") (pintype "input"))
    )
    (net (code "73") (name "Net-(E17B-CLR)") (class "Default")
      (node (ref "E17") (pin "8") (pinfunction "CLR_8") (pintype "input"))
      (node (ref "E18") (pin "13") (pinfunction "O_13") (pintype "output"))
    )
    (net (code "74") (name "Net-(E17B-J)") (class "Default")
      (node (ref "E17") (pin "12") (pinfunction "K_12") (pintype "input"))
      (node (ref "E17") (pin "9") (pinfunction "J_9") (pintype "input"))
      (node (ref "E8") (pin "8") (pinfunction "O_8") (pintype "output"))
      (node (ref "IC7") (pin "7") (pinfunction "I1_7") (pintype "input"))
    )
    (net (code "75") (name "Net-(E19A-CLR)") (class "Default")
      (node (ref "E19") (pin "1") (pinfunction "CLR_1") (pintype "input"))
      (node (ref "E26") (pin "1") (pinfunction "O_1") (pintype "output"))
    )
    (net (code "76") (name "Net-(E19B-CLR)") (class "Default")
      (node (ref "E19") (pin "13") (pinfunction "CLR_13") (pintype "input"))
      (node (ref "E26") (pin "4") (pinfunction "O_4") (pintype "output"))
    )
    (net (code "77") (name "Net-(E20A-I1)") (class "Default")
      (node (ref "E20") (pin "2") (pinfunction "I1_2") (pintype "input"))
      (node (ref "E20") (pin "6") (pinfunction "O_6") (pintype "output"))
    )
    (net (code "78") (name "Net-(E20A-O)") (class "Default")
      (node (ref "E20") (pin "3") (pinfunction "O_3") (pintype "output"))
      (node (ref "IC10") (pin "1") (pinfunction "I0_1") (pintype "input"))
      (node (ref "IC10") (pin "2") (pinfunction "I1_2") (pintype "input"))
    )
    (net (code "79") (name "Net-(E21A-J)") (class "Default")
      (node (ref "E21") (pin "2") (pinfunction "J_2") (pintype "input"))
      (node (ref "E21") (pin "3") (pinfunction "K_3") (pintype "input"))
      (node (ref "E22") (pin "12") (pinfunction "QD_12") (pintype "output"))
      (node (ref "IC4") (pin "6") (pinfunction "I0_6") (pintype "input"))
    )
    (net (code "80") (name "Net-(E21A-QA)") (class "Default")
      (node (ref "E21") (pin "15") (pinfunction "QA_15") (pintype "output"))
      (node (ref "IC3") (pin "6") (pinfunction "I0_6") (pintype "input"))
    )
    (net (code "81") (name "Net-(E21A-QB)") (class "Default")
      (node (ref "E21") (pin "14") (pinfunction "QB_14") (pintype "output"))
      (node (ref "IC3") (pin "1") (pinfunction "I0_1") (pintype "input"))
    )
    (net (code "82") (name "Net-(E21A-QC)") (class "Default")
      (node (ref "E21") (pin "13") (pinfunction "QC_13") (pintype "output"))
      (node (ref "IC4") (pin "1") (pinfunction "I0_1") (pintype "input"))
    )
    (net (code "83") (name "Net-(E22A-QA)") (class "Default")
      (node (ref "E22") (pin "15") (pinfunction "QA_15") (pintype "output"))
      (node (ref "IC2") (pin "1") (pinfunction "I0_1") (pintype "input"))
    )
    (net (code "84") (name "Net-(E22A-QB)") (class "Default")
      (node (ref "E22") (pin "14") (pinfunction "QB_14") (pintype "output"))
      (node (ref "IC5") (pin "6") (pinfunction "I0_6") (pintype "input"))
    )
    (net (code "85") (name "Net-(E22A-QC)") (class "Default")
      (node (ref "E22") (pin "13") (pinfunction "QC_13") (pintype "output"))
      (node (ref "IC5") (pin "1") (pinfunction "I0_1") (pintype "input"))
    )
    (net (code "86") (name "Net-(E23A-QA)") (class "Default")
      (node (ref "E23") (pin "15") (pinfunction "QA_15") (pintype "output"))
      (node (ref "IC2") (pin "6") (pinfunction "I0_6") (pintype "input"))
    )
    (net (code "87") (name "Net-(E23A-QB)") (class "Default")
      (node (ref "E23") (pin "14") (pinfunction "QB_14") (pintype "output"))
      (node (ref "IC1") (pin "1") (pinfunction "I0_1") (pintype "input"))
    )
    (net (code "88") (name "Net-(E23A-QC)") (class "Default")
      (node (ref "E23") (pin "13") (pinfunction "QC_13") (pintype "output"))
      (node (ref "IC6") (pin "6") (pinfunction "I0_6") (pintype "input"))
    )
    (net (code "89") (name "Net-(E24A-I1)") (class "Default")
      (node (ref "E24") (pin "2") (pinfunction "I1_2") (pintype "input"))
      (node (ref "E35") (pin "13") (pinfunction "O_13") (pintype "output"))
      (node (ref "IC1") (pin "7") (pinfunction "I1_7") (pintype "input"))
      (node (ref "IC2") (pin "2") (pinfunction "I1_2") (pintype "input"))
      (node (ref "IC3") (pin "2") (pinfunction "I1_2") (pintype "input"))
      (node (ref "IC3") (pin "7") (pinfunction "I1_7") (pintype "input"))
      (node (ref "IC4") (pin "2") (pinfunction "I1_2") (pintype "input"))
      (node (ref "IC4") (pin "7") (pinfunction "I1_7") (pintype "input"))
      (node (ref "IC5") (pin "2") (pinfunction "I1_2") (pintype "input"))
      (node (ref "IC5") (pin "7") (pinfunction "I1_7") (pintype "input"))
    )
    (net (code "90") (name "Net-(E24A-O)") (class "Default")
      (node (ref "E24") (pin "3") (pinfunction "O_3") (pintype "output"))
      (node (ref "IC1") (pin "2") (pinfunction "I1_2") (pintype "input"))
      (node (ref "IC2") (pin "7") (pinfunction "I1_7") (pintype "input"))
      (node (ref "IC6") (pin "2") (pinfunction "I1_2") (pintype "input"))
      (node (ref "IC6") (pin "7") (pinfunction "I1_7") (pintype "input"))
    )
    (net (code "91") (name "Net-(E24B-O)") (class "Default")
      (node (ref "E24") (pin "6") (pinfunction "O_6") (pintype "output"))
      (node (ref "E32") (pin "1") (pinfunction "I0_1") (pintype "input"))
    )
    (net (code "92") (name "Net-(E24C-O)") (class "Default")
      (node (ref "E24") (pin "8") (pinfunction "O_8") (pintype "output"))
      (node (ref "E30") (pin "13") (pinfunction "CLR_13") (pintype "input"))
    )
    (net (code "93") (name "Net-(E25C-O)") (class "Default")
      (node (ref "E25") (pin "6") (pinfunction "O_6") (pintype "output"))
      (node (ref "E31") (pin "1") (pinfunction "I0_1") (pintype "input"))
      (node (ref "E31") (pin "2") (pinfunction "I1_2") (pintype "input"))
    )
    (net (code "94") (name "Net-(E25D-O)") (class "Default")
      (node (ref "E25") (pin "8") (pinfunction "O_8") (pintype "output"))
      (node (ref "E31") (pin "13") (pinfunction "I3_13") (pintype "input"))
    )
    (net (code "95") (name "Net-(E25E-O)") (class "Default")
      (node (ref "E25") (pin "10") (pinfunction "O_10") (pintype "output"))
      (node (ref "E26") (pin "11") (pinfunction "I0_11") (pintype "input"))
      (node (ref "E26") (pin "12") (pinfunction "I1_12") (pintype "input"))
    )
    (net (code "96") (name "Net-(E25F-O)") (class "Default")
      (node (ref "E25") (pin "12") (pinfunction "O_12") (pintype "output"))
      (node (ref "E36") (pin "11") (pinfunction "I0_11") (pintype "input"))
      (node (ref "E36") (pin "12") (pinfunction "I1_12") (pintype "input"))
    )
    (net (code "97") (name "Net-(E26C-O)") (class "Default")
      (node (ref "E26") (pin "10") (pinfunction "O_10") (pintype "output"))
      (node (ref "E6") (pin "13") (pinfunction "CLR_13") (pintype "input"))
    )
    (net (code "98") (name "Net-(E30A-Q)") (class "Default")
      (node (ref "E30") (pin "5") (pinfunction "Q_5") (pintype "output"))
      (node (ref "IC10") (pin "7") (pinfunction "I1_7") (pintype "input"))
    )
    (net (code "99") (name "Net-(E30B-CLK)") (class "Default")
      (node (ref "E30") (pin "11") (pinfunction "CLK_11") (pintype "input"))
      (node (ref "IC9") (pin "3") (pinfunction "O_3") (pintype "open_collector"))
      (node (ref "R18") (pin "1") (pinfunction "1_1") (pintype "passive"))
    )
    (net (code "100") (name "Net-(E31A-O)") (class "Default")
      (node (ref "E31") (pin "6") (pinfunction "O_6") (pintype "output"))
      (node (ref "IC9") (pin "1") (pinfunction "I0_1") (pintype "input"))
    )
    (net (code "101") (name "Net-(E31B-O)") (class "Default")
      (node (ref "E31") (pin "8") (pinfunction "O_8") (pintype "output"))
      (node (ref "IC9") (pin "2") (pinfunction "I1_2") (pintype "input"))
    )
    (net (code "102") (name "Net-(E32A-O)") (class "Default")
      (node (ref "E32") (pin "12") (pinfunction "O_12") (pintype "output"))
      (node (ref "E32") (pin "4") (pinfunction "I1_4") (pintype "input"))
      (node (ref "E32") (pin "5") (pinfunction "I2_5") (pintype "input"))
    )
    (net (code "103") (name "Net-(E32C-O)") (class "Default")
      (node (ref "E32") (pin "8") (pinfunction "O_8") (pintype "output"))
      (node (ref "E35") (pin "11") (pinfunction "I0_11") (pintype "input"))
    )
    (net (code "104") (name "Net-(PAD10-P)") (class "Default")
      (node (ref "E38") (pin "1") (pinfunction "1_1") (pintype "passive"))
      (node (ref "PAD10") (pin "1") (pinfunction "P_1") (pintype "passive"))
    )
    (net (code "105") (name "Net-(PAD11-P)") (class "Default")
      (node (ref "E38") (pin "2") (pinfunction "2_2") (pintype "passive"))
      (node (ref "PAD11") (pin "1") (pinfunction "P_1") (pintype "passive"))
    )
    (net (code "106") (name "Net-(PAD12-P)") (class "Default")
      (node (ref "E38") (pin "3") (pinfunction "3_3") (pintype "passive"))
      (node (ref "PAD12") (pin "1") (pinfunction "P_1") (pintype "passive"))
    )
    (net (code "107") (name "Net-(PAD13-P)") (class "Default")
      (node (ref "E38") (pin "4") (pinfunction "4_4") (pintype "passive"))
      (node (ref "PAD13") (pin "1") (pinfunction "P_1") (pintype "passive"))
    )
    (net (code "108") (name "Net-(PAD14-P)") (class "Default")
      (node (ref "E38") (pin "5") (pinfunction "5_5") (pintype "passive"))
      (node (ref "PAD14") (pin "1") (pinfunction "P_1") (pintype "passive"))
    )
    (net (code "109") (name "Net-(PAD15-P)") (class "Default")
      (node (ref "E38") (pin "6") (pinfunction "6_6") (pintype "passive"))
      (node (ref "PAD15") (pin "1") (pinfunction "P_1") (pintype "passive"))
    )
    (net (code "110") (name "Net-(PAD16-P)") (class "Default")
      (node (ref "E38") (pin "7") (pinfunction "7_7") (pintype "passive"))
      (node (ref "PAD16") (pin "1") (pinfunction "P_1") (pintype "passive"))
    )
    (net (code "111") (name "Net-(PAD17-P)") (class "Default")
      (node (ref "E38") (pin "8") (pinfunction "8_8") (pintype "passive"))
      (node (ref "PAD17") (pin "1") (pinfunction "P_1") (pintype "passive"))
    )
    (net (code "112") (name "Net-(PAD18-P)") (class "Default")
      (node (ref "E40") (pin "1") (pinfunction "1_1") (pintype "passive"))
      (node (ref "PAD18") (pin "1") (pinfunction "P_1") (pintype "passive"))
    )
    (net (code "113") (name "Net-(PAD19-P)") (class "Default")
      (node (ref "E40") (pin "2") (pinfunction "2_2") (pintype "passive"))
      (node (ref "PAD19") (pin "1") (pinfunction "P_1") (pintype "passive"))
    )
    (net (code "114") (name "Net-(PAD20-P)") (class "Default")
      (node (ref "E38") (pin "16") (pinfunction "16_16") (pintype "passive"))
      (node (ref "PAD20") (pin "1") (pinfunction "P_1") (pintype "passive"))
    )
    (net (code "115") (name "Net-(PAD21-P)") (class "Default")
      (node (ref "E38") (pin "15") (pinfunction "15_15") (pintype "passive"))
      (node (ref "PAD21") (pin "1") (pinfunction "P_1") (pintype "passive"))
    )
    (net (code "116") (name "Net-(PAD22-P)") (class "Default")
      (node (ref "E38") (pin "14") (pinfunction "14_14") (pintype "passive"))
      (node (ref "PAD22") (pin "1") (pinfunction "P_1") (pintype "passive"))
    )
    (net (code "117") (name "Net-(PAD23-P)") (class "Default")
      (node (ref "E38") (pin "13") (pinfunction "13_13") (pintype "passive"))
      (node (ref "PAD23") (pin "1") (pinfunction "P_1") (pintype "passive"))
    )
    (net (code "118") (name "Net-(PAD24-P)") (class "Default")
      (node (ref "E38") (pin "12") (pinfunction "12_12") (pintype "passive"))
      (node (ref "PAD24") (pin "1") (pinfunction "P_1") (pintype "passive"))
    )
    (net (code "119") (name "Net-(PAD25-P)") (class "Default")
      (node (ref "E38") (pin "11") (pinfunction "11_11") (pintype "passive"))
      (node (ref "PAD25") (pin "1") (pinfunction "P_1") (pintype "passive"))
    )
    (net (code "120") (name "Net-(PAD26-P)") (class "Default")
      (node (ref "E38") (pin "10") (pinfunction "10_10") (pintype "passive"))
      (node (ref "PAD26") (pin "1") (pinfunction "P_1") (pintype "passive"))
    )
    (net (code "121") (name "Net-(PAD27-P)") (class "Default")
      (node (ref "E38") (pin "9") (pinfunction "9_9") (pintype "passive"))
      (node (ref "PAD27") (pin "1") (pinfunction "P_1") (pintype "passive"))
    )
    (net (code "122") (name "Net-(PAD28-P)") (class "Default")
      (node (ref "E40") (pin "3") (pinfunction "3_3") (pintype "passive"))
      (node (ref "PAD28") (pin "1") (pinfunction "P_1") (pintype "passive"))
    )
    (net (code "123") (name "Net-(PAD29-P)") (class "Default")
      (node (ref "E40") (pin "4") (pinfunction "4_4") (pintype "passive"))
      (node (ref "PAD29") (pin "1") (pinfunction "P_1") (pintype "passive"))
    )
    (net (code "124") (name "Net-(PAD30-P)") (class "Default")
      (node (ref "E40") (pin "5") (pinfunction "5_5") (pintype "passive"))
      (node (ref "PAD30") (pin "1") (pinfunction "P_1") (pintype "passive"))
    )
    (net (code "125") (name "Net-(PAD31-P)") (class "Default")
      (node (ref "E40") (pin "6") (pinfunction "6_6") (pintype "passive"))
      (node (ref "PAD31") (pin "1") (pinfunction "P_1") (pintype "passive"))
    )
    (net (code "126") (name "Net-(PAD32-P)") (class "Default")
      (node (ref "E40") (pin "7") (pinfunction "7_7") (pintype "passive"))
      (node (ref "PAD32") (pin "1") (pinfunction "P_1") (pintype "passive"))
    )
    (net (code "127") (name "Net-(PAD33-P)") (class "Default")
      (node (ref "E40") (pin "8") (pinfunction "8_8") (pintype "passive"))
      (node (ref "PAD33") (pin "1") (pinfunction "P_1") (pintype "passive"))
    )
    (net (code "128") (name "Net-(PAD34-P)") (class "Default")
      (node (ref "E40") (pin "16") (pinfunction "16_16") (pintype "passive"))
      (node (ref "PAD34") (pin "1") (pinfunction "P_1") (pintype "passive"))
    )
    (net (code "129") (name "Net-(PAD35-P)") (class "Default")
      (node (ref "E40") (pin "15") (pinfunction "15_15") (pintype "passive"))
      (node (ref "PAD35") (pin "1") (pinfunction "P_1") (pintype "passive"))
    )
    (net (code "130") (name "Net-(PAD36-P)") (class "Default")
      (node (ref "E40") (pin "14") (pinfunction "14_14") (pintype "passive"))
      (node (ref "PAD36") (pin "1") (pinfunction "P_1") (pintype "passive"))
    )
    (net (code "131") (name "Net-(PAD37-P)") (class "Default")
      (node (ref "E40") (pin "13") (pinfunction "13_13") (pintype "passive"))
      (node (ref "PAD37") (pin "1") (pinfunction "P_1") (pintype "passive"))
    )
    (net (code "132") (name "Net-(PAD38-P)") (class "Default")
      (node (ref "E40") (pin "12") (pinfunction "12_12") (pintype "passive"))
      (node (ref "PAD38") (pin "1") (pinfunction "P_1") (pintype "passive"))
    )
    (net (code "133") (name "Net-(PAD39-P)") (class "Default")
      (node (ref "E40") (pin "11") (pinfunction "11_11") (pintype "passive"))
      (node (ref "PAD39") (pin "1") (pinfunction "P_1") (pintype "passive"))
    )
    (net (code "134") (name "Net-(PAD40-P)") (class "Default")
      (node (ref "E40") (pin "10") (pinfunction "10_10") (pintype "passive"))
      (node (ref "PAD40") (pin "1") (pinfunction "P_1") (pintype "passive"))
    )
    (net (code "135") (name "Net-(PAD41-P)") (class "Default")
      (node (ref "E40") (pin "9") (pinfunction "9_9") (pintype "passive"))
      (node (ref "PAD41") (pin "1") (pinfunction "P_1") (pintype "passive"))
    )
    (net (code "136") (name "Net-(PAD42-P)") (class "Default")
      (node (ref "E39") (pin "1") (pinfunction "1_1") (pintype "passive"))
      (node (ref "PAD42") (pin "1") (pinfunction "P_1") (pintype "passive"))
    )
    (net (code "137") (name "Net-(PAD43-P)") (class "Default")
      (node (ref "E39") (pin "2") (pinfunction "2_2") (pintype "passive"))
      (node (ref "PAD43") (pin "1") (pinfunction "P_1") (pintype "passive"))
    )
    (net (code "138") (name "Net-(PAD44-P)") (class "Default")
      (node (ref "E39") (pin "3") (pinfunction "3_3") (pintype "passive"))
      (node (ref "PAD44") (pin "1") (pinfunction "P_1") (pintype "passive"))
    )
    (net (code "139") (name "Net-(PAD45-P)") (class "Default")
      (node (ref "E39") (pin "4") (pinfunction "4_4") (pintype "passive"))
      (node (ref "PAD45") (pin "1") (pinfunction "P_1") (pintype "passive"))
    )
    (net (code "140") (name "Net-(PAD46-P)") (class "Default")
      (node (ref "E39") (pin "5") (pinfunction "5_5") (pintype "passive"))
      (node (ref "PAD46") (pin "1") (pinfunction "P_1") (pintype "passive"))
    )
    (net (code "141") (name "Net-(PAD47-P)") (class "Default")
      (node (ref "E39") (pin "6") (pinfunction "6_6") (pintype "passive"))
      (node (ref "PAD47") (pin "1") (pinfunction "P_1") (pintype "passive"))
    )
    (net (code "142") (name "Net-(PAD48-P)") (class "Default")
      (node (ref "E39") (pin "7") (pinfunction "7_7") (pintype "passive"))
      (node (ref "PAD48") (pin "1") (pinfunction "P_1") (pintype "passive"))
    )
    (net (code "143") (name "Net-(PAD49-P)") (class "Default")
      (node (ref "E39") (pin "8") (pinfunction "8_8") (pintype "passive"))
      (node (ref "PAD49") (pin "1") (pinfunction "P_1") (pintype "passive"))
    )
    (net (code "144") (name "Net-(PAD50-P)") (class "Default")
      (node (ref "E39") (pin "16") (pinfunction "16_16") (pintype "passive"))
      (node (ref "PAD50") (pin "1") (pinfunction "P_1") (pintype "passive"))
    )
    (net (code "145") (name "Net-(PAD51-P)") (class "Default")
      (node (ref "E39") (pin "15") (pinfunction "15_15") (pintype "passive"))
      (node (ref "PAD51") (pin "1") (pinfunction "P_1") (pintype "passive"))
    )
    (net (code "146") (name "Net-(PAD52-P)") (class "Default")
      (node (ref "E39") (pin "14") (pinfunction "14_14") (pintype "passive"))
      (node (ref "PAD52") (pin "1") (pinfunction "P_1") (pintype "passive"))
    )
    (net (code "147") (name "Net-(PAD53-P)") (class "Default")
      (node (ref "E39") (pin "13") (pinfunction "13_13") (pintype "passive"))
      (node (ref "PAD53") (pin "1") (pinfunction "P_1") (pintype "passive"))
    )
    (net (code "148") (name "Net-(PAD54-P)") (class "Default")
      (node (ref "E39") (pin "12") (pinfunction "12_12") (pintype "passive"))
      (node (ref "PAD54") (pin "1") (pinfunction "P_1") (pintype "passive"))
    )
    (net (code "149") (name "Net-(PAD55-P)") (class "Default")
      (node (ref "E39") (pin "11") (pinfunction "11_11") (pintype "passive"))
      (node (ref "PAD55") (pin "1") (pinfunction "P_1") (pintype "passive"))
    )
    (net (code "150") (name "Net-(PAD56-P)") (class "Default")
      (node (ref "E39") (pin "10") (pinfunction "10_10") (pintype "passive"))
      (node (ref "PAD56") (pin "1") (pinfunction "P_1") (pintype "passive"))
    )
    (net (code "151") (name "Net-(PAD57-P)") (class "Default")
      (node (ref "E39") (pin "9") (pinfunction "9_9") (pintype "passive"))
      (node (ref "PAD57") (pin "1") (pinfunction "P_1") (pintype "passive"))
    )
    (net (code "152") (name "PARITY") (class "Default")
      (node (ref "E15") (pin "1") (pinfunction "I0_1") (pintype "input"))
      (node (ref "E15") (pin "13") (pinfunction "I1_13") (pintype "input"))
      (node (ref "E15") (pin "2") (pinfunction "I1_2") (pintype "input"))
      (node (ref "E4") (pin "15") (pinfunction "RCO_15") (pintype "output"))
    )
    (net (code "153") (name "RD") (class "Default")
      (node (ref "E25") (pin "1") (pinfunction "I_1") (pintype "input"))
      (node (ref "E32") (pin "10") (pinfunction "I1_10") (pintype "input"))
      (node (ref "E35") (pin "10") (pinfunction "O_10") (pintype "output"))
    )
    (net (code "154") (name "RUN") (class "Default")
      (node (ref "E18") (pin "11") (pinfunction "I0_11") (pintype "input"))
      (node (ref "E30") (pin "9") (pinfunction "Q_9") (pintype "output"))
      (node (ref "IC9") (pin "6") (pinfunction "I0_6") (pintype "input"))
      (node (ref "IC9") (pin "7") (pinfunction "I1_7") (pintype "input"))
    )
    (net (code "155") (name "RX_DATA") (class "Default")
      (node (ref "E22") (pin "2") (pinfunction "J_2") (pintype "input"))
      (node (ref "E22") (pin "3") (pinfunction "K_3") (pintype "input"))
      (node (ref "E35") (pin "1") (pinfunction "O_1") (pintype "output"))
    )
    (net (code "156") (name "SHIFT") (class "Default")
      (node (ref "E32") (pin "3") (pinfunction "I0_3") (pintype "input"))
      (node (ref "E35") (pin "4") (pinfunction "O_4") (pintype "output"))
    )
    (net (code "157") (name "TR_SKIP") (class "Default")
      (node (ref "E18") (pin "1") (pinfunction "O_1") (pintype "output"))
      (node (ref "E20") (pin "1") (pinfunction "I0_1") (pintype "input"))
      (node (ref "E26") (pin "3") (pinfunction "I1_3") (pintype "input"))
    )
    (net (code "158") (name "VCC") (class "Default")
      (node (ref "C1") (pin "1") (pinfunction "1_1") (pintype "passive"))
      (node (ref "C10") (pin "1") (pinfunction "1_1") (pintype "passive"))
      (node (ref "C11") (pin "1") (pinfunction "1_1") (pintype "passive"))
      (node (ref "C12") (pin "1") (pinfunction "1_1") (pintype "passive"))
      (node (ref "C13") (pin "1") (pinfunction "1_1") (pintype "passive"))
      (node (ref "C14") (pin "1") (pinfunction "1_1") (pintype "passive"))
      (node (ref "C15") (pin "1") (pinfunction "1_1") (pintype "passive"))
      (node (ref "C16") (pin "1") (pinfunction "1_1") (pintype "passive"))
      (node (ref "C17") (pin "1") (pinfunction "1_1") (pintype "passive"))
      (node (ref "C18") (pin "1") (pinfunction "1_1") (pintype "passive"))
      (node (ref "C19") (pin "1") (pinfunction "1_1") (pintype "passive"))
      (node (ref "C2") (pin "1") (pinfunction "1_1") (pintype "passive"))
      (node (ref "C20") (pin "1") (pinfunction "1_1") (pintype "passive"))
      (node (ref "C21") (pin "1") (pinfunction "1_1") (pintype "passive"))
      (node (ref "C22") (pin "1") (pinfunction "1_1") (pintype "passive"))
      (node (ref "C23") (pin "1") (pinfunction "1_1") (pintype "passive"))
      (node (ref "C24") (pin "1") (pinfunction "1_1") (pintype "passive"))
      (node (ref "C25") (pin "1") (pinfunction "1_1") (pintype "passive"))
      (node (ref "C26") (pin "1") (pinfunction "1_1") (pintype "passive"))
      (node (ref "C27") (pin "1") (pinfunction "1_1") (pintype "passive"))
      (node (ref "C28") (pin "1") (pinfunction "1_1") (pintype "passive"))
      (node (ref "C29") (pin "1") (pinfunction "1_1") (pintype "passive"))
      (node (ref "C3") (pin "1") (pinfunction "1_1") (pintype "passive"))
      (node (ref "C30") (pin "1") (pinfunction "1_1") (pintype "passive"))
      (node (ref "C31") (pin "1") (pinfunction "1_1") (pintype "passive"))
      (node (ref "C32") (pin "1") (pinfunction "1_1") (pintype "passive"))
      (node (ref "C33") (pin "1") (pinfunction "1_1") (pintype "passive"))
      (node (ref "C34") (pin "1") (pinfunction "1_1") (pintype "passive"))
      (node (ref "C35") (pin "1") (pinfunction "1_1") (pintype "passive"))
      (node (ref "C36") (pin "1") (pinfunction "1_1") (pintype "passive"))
      (node (ref "C37") (pin "1") (pinfunction "1_1") (pintype "passive"))
      (node (ref "C38") (pin "1") (pinfunction "1_1") (pintype "passive"))
      (node (ref "C39") (pin "1") (pinfunction "1_1") (pintype "passive"))
      (node (ref "C4") (pin "1") (pinfunction "1_1") (pintype "passive"))
      (node (ref "C40") (pin "+") (pinfunction "+_+") (pintype "passive"))
      (node (ref "C5") (pin "1") (pinfunction "1_1") (pintype "passive"))
      (node (ref "C6") (pin "1") (pinfunction "1_1") (pintype "passive"))
      (node (ref "C7") (pin "1") (pinfunction "1_1") (pintype "passive"))
      (node (ref "C8") (pin "1") (pinfunction "1_1") (pintype "passive"))
      (node (ref "C9") (pin "1") (pinfunction "1_1") (pintype "passive"))
      (node (ref "E1") (pin "4") (pinfunction "I1_4") (pintype "input"))
      (node (ref "E1") (pin "5") (pinfunction "I2_5") (pintype "input"))
      (node (ref "E14") (pin "6") (pinfunction "G1_6") (pintype "input"))
      (node (ref "E17") (pin "1") (pinfunction "CLK_1") (pintype "input"))
      (node (ref "E17") (pin "2") (pinfunction "PRE_2") (pintype "input"))
      (node (ref "E17") (pin "3") (pinfunction "CLR_3") (pintype "input"))
      (node (ref "E17") (pin "4") (pinfunction "J_4") (pintype "input"))
      (node (ref "E17") (pin "7") (pinfunction "PRE_7") (pintype "input"))
      (node (ref "E19") (pin "12") (pinfunction "D_12") (pintype "input"))
      (node (ref "E19") (pin "2") (pinfunction "D_2") (pintype "input"))
      (node (ref "E2") (pin "10") (pinfunction "PRE_10") (pintype "input"))
      (node (ref "E20") (pin "10") (pinfunction "I1_10") (pintype "input"))
      (node (ref "E20") (pin "9") (pinfunction "I0_9") (pintype "input"))
      (node (ref "E25") (pin "11") (pinfunction "I_11") (pintype "input"))
      (node (ref "E25") (pin "13") (pinfunction "I_13") (pintype "input"))
      (node (ref "E30") (pin "10") (pinfunction "PRE_10") (pintype "input"))
      (node (ref "E30") (pin "12") (pinfunction "D_12") (pintype "input"))
      (node (ref "E30") (pin "4") (pinfunction "PRE_4") (pintype "input"))
      (node (ref "E6") (pin "12") (pinfunction "D_12") (pintype "input"))
      (node (ref "E6") (pin "4") (pinfunction "PRE_4") (pintype "input"))
      (node (ref "R1") (pin "2") (pinfunction "2_2") (pintype "passive"))
      (node (ref "R18") (pin "2") (pinfunction "2_2") (pintype "passive"))
      (node (ref "R19") (pin "1") (pinfunction "1_1") (pintype "passive"))
      (node (ref "R2") (pin "2") (pinfunction "2_2") (pintype "passive"))
      (node (ref "R20") (pin "2") (pinfunction "2_2") (pintype "passive"))
      (node (ref "R3") (pin "2") (pinfunction "2_2") (pintype "passive"))
      (node (ref "R4") (pin "2") (pinfunction "2_2") (pintype "passive"))
      (node (ref "R5") (pin "2") (pinfunction "2_2") (pintype "passive"))
      (node (ref "R6") (pin "2") (pinfunction "2_2") (pintype "passive"))
      (node (ref "R7") (pin "2") (pinfunction "2_2") (pintype "passive"))
      (node (ref "R8") (pin "2") (pinfunction "2_2") (pintype "passive"))
      (node (ref "R9") (pin "2") (pinfunction "2_2") (pintype "passive"))
      (node (ref "SL1") (pin "1") (pinfunction "S_1") (pintype "passive"))
    )
    (net (code "159") (name "WRT") (class "Default")
      (node (ref "E10") (pin "5") (pinfunction "I2_5") (pintype "input"))
      (node (ref "E15") (pin "10") (pinfunction "I1_10") (pintype "input"))
      (node (ref "E25") (pin "2") (pinfunction "O_2") (pintype "output"))
      (node (ref "IC7") (pin "6") (pinfunction "I0_6") (pintype "input"))
    )
    (net (code "160") (name "XDR2") (class "Default")
      (node (ref "E10") (pin "2") (pinfunction "I1_2") (pintype "input"))
      (node (ref "E5") (pin "12") (pinfunction "I0_12") (pintype "input"))
      (node (ref "E5") (pin "8") (pinfunction "O_8") (pintype "output"))
    )
    (net (code "161") (name "XFER_REQ") (class "Default")
      (node (ref "E19") (pin "3") (pinfunction "CLK_3") (pintype "input"))
      (node (ref "E20") (pin "12") (pinfunction "I0_12") (pintype "input"))
      (node (ref "E36") (pin "4") (pinfunction "O_4") (pintype "output"))
    )
    (net (code "162") (name "unconnected-(D34L1-2-PadB)") (class "Default")
      (node (ref "D34L1") (pin "B") (pinfunction "2_B") (pintype "bidirectional"))
    )
    (net (code "163") (name "unconnected-(D34L1-34-PadNN)") (class "Default")
      (node (ref "D34L1") (pin "NN") (pinfunction "34_NN") (pintype "bidirectional"))
    )
    (net (code "164") (name "unconnected-(D34L1-38-PadTT)") (class "Default")
      (node (ref "D34L1") (pin "TT") (pinfunction "38_TT") (pintype "bidirectional"))
    )
    (net (code "165") (name "unconnected-(D34L1-40-PadVV)") (class "Default")
      (node (ref "D34L1") (pin "VV") (pinfunction "40_VV") (pintype "bidirectional"))
    )
    (net (code "166") (name "unconnected-(D34L2-2-PadB)") (class "Default")
      (node (ref "D34L2") (pin "B") (pinfunction "2_B") (pintype "bidirectional"))
    )
    (net (code "167") (name "unconnected-(D34L2-34-PadNN)") (class "Default")
      (node (ref "D34L2") (pin "NN") (pinfunction "34_NN") (pintype "bidirectional"))
    )
    (net (code "168") (name "unconnected-(D34L2-38-PadTT)") (class "Default")
      (node (ref "D34L2") (pin "TT") (pinfunction "38_TT") (pintype "bidirectional"))
    )
    (net (code "169") (name "unconnected-(D34L2-40-PadVV)") (class "Default")
      (node (ref "D34L2") (pin "VV") (pinfunction "40_VV") (pintype "bidirectional"))
    )
    (net (code "170") (name "unconnected-(D35L1-2-PadB)") (class "Default")
      (node (ref "D35L1") (pin "B") (pinfunction "2_B") (pintype "bidirectional"))
    )
    (net (code "171") (name "unconnected-(D35L1-40-PadVV)") (class "Default")
      (node (ref "D35L1") (pin "VV") (pinfunction "40_VV") (pintype "bidirectional"))
    )
    (net (code "172") (name "unconnected-(D35L2-2-PadB)") (class "Default")
      (node (ref "D35L2") (pin "B") (pinfunction "2_B") (pintype "bidirectional"))
    )
    (net (code "173") (name "unconnected-(D35L2-40-PadVV)") (class "Default")
      (node (ref "D35L2") (pin "VV") (pinfunction "40_VV") (pintype "bidirectional"))
    )
    (net (code "174") (name "unconnected-(D36L1-2-PadB)") (class "Default")
      (node (ref "D36L1") (pin "B") (pinfunction "2_B") (pintype "bidirectional"))
    )
    (net (code "175") (name "unconnected-(D36L1-40-PadVV)") (class "Default")
      (node (ref "D36L1") (pin "VV") (pinfunction "40_VV") (pintype "bidirectional"))
    )
    (net (code "176") (name "unconnected-(D36L2-2-PadB)") (class "Default")
      (node (ref "D36L2") (pin "B") (pinfunction "2_B") (pintype "bidirectional"))
    )
    (net (code "177") (name "unconnected-(D36L2-40-PadVV)") (class "Default")
      (node (ref "D36L2") (pin "VV") (pinfunction "40_VV") (pintype "bidirectional"))
    )
    (net (code "178") (name "unconnected-(E2A-Q-Pad5)") (class "Default")
      (node (ref "E2") (pin "5") (pinfunction "Q_5") (pintype "output"))
    )
    (net (code "179") (name "unconnected-(E4A-QA-Pad14)") (class "Default")
      (node (ref "E4") (pin "14") (pinfunction "QA_14") (pintype "output"))
    )
    (net (code "180") (name "unconnected-(E4A-QB-Pad13)") (class "Default")
      (node (ref "E4") (pin "13") (pinfunction "QB_13") (pintype "output"))
    )
    (net (code "181") (name "unconnected-(E4A-QC-Pad12)") (class "Default")
      (node (ref "E4") (pin "12") (pinfunction "QC_12") (pintype "output"))
    )
    (net (code "182") (name "unconnected-(E4A-QD-Pad11)") (class "Default")
      (node (ref "E4") (pin "11") (pinfunction "QD_11") (pintype "output"))
    )
    (net (code "183") (name "unconnected-(E6B-~{Q}-Pad8)") (class "Default")
      (node (ref "E6") (pin "8") (pinfunction "~{Q}_8") (pintype "output"))
    )
    (net (code "184") (name "unconnected-(E11A-Y0-Pad15)") (class "Default")
      (node (ref "E11") (pin "15") (pinfunction "Y0_15") (pintype "output"))
    )
    (net (code "185") (name "unconnected-(E11A-Y2-Pad13)") (class "Default")
      (node (ref "E11") (pin "13") (pinfunction "Y2_13") (pintype "output"))
    )
    (net (code "186") (name "unconnected-(E11A-Y3-Pad12)") (class "Default")
      (node (ref "E11") (pin "12") (pinfunction "Y3_12") (pintype "output"))
    )
    (net (code "187") (name "unconnected-(E11A-Y4-Pad11)") (class "Default")
      (node (ref "E11") (pin "11") (pinfunction "Y4_11") (pintype "output"))
    )
    (net (code "188") (name "unconnected-(E11A-Y5-Pad10)") (class "Default")
      (node (ref "E11") (pin "10") (pinfunction "Y5_10") (pintype "output"))
    )
    (net (code "189") (name "unconnected-(E11A-Y6-Pad9)") (class "Default")
      (node (ref "E11") (pin "9") (pinfunction "Y6_9") (pintype "output"))
    )
    (net (code "190") (name "unconnected-(E12A-Y0-Pad15)") (class "Default")
      (node (ref "E12") (pin "15") (pinfunction "Y0_15") (pintype "output"))
    )
    (net (code "191") (name "unconnected-(E12A-Y1-Pad14)") (class "Default")
      (node (ref "E12") (pin "14") (pinfunction "Y1_14") (pintype "output"))
    )
    (net (code "192") (name "unconnected-(E12A-Y4-Pad11)") (class "Default")
      (node (ref "E12") (pin "11") (pinfunction "Y4_11") (pintype "output"))
    )
    (net (code "193") (name "unconnected-(E12A-Y5-Pad10)") (class "Default")
      (node (ref "E12") (pin "10") (pinfunction "Y5_10") (pintype "output"))
    )
    (net (code "194") (name "unconnected-(E12A-Y6-Pad9)") (class "Default")
      (node (ref "E12") (pin "9") (pinfunction "Y6_9") (pintype "output"))
    )
    (net (code "195") (name "unconnected-(E12A-Y7-Pad7)") (class "Default")
      (node (ref "E12") (pin "7") (pinfunction "Y7_7") (pintype "output"))
    )
    (net (code "196") (name "unconnected-(E13A-Y0-Pad15)") (class "Default")
      (node (ref "E13") (pin "15") (pinfunction "Y0_15") (pintype "output"))
    )
    (net (code "197") (name "unconnected-(E13A-Y1-Pad14)") (class "Default")
      (node (ref "E13") (pin "14") (pinfunction "Y1_14") (pintype "output"))
    )
    (net (code "198") (name "unconnected-(E13A-Y2-Pad13)") (class "Default")
      (node (ref "E13") (pin "13") (pinfunction "Y2_13") (pintype "output"))
    )
    (net (code "199") (name "unconnected-(E13A-Y3-Pad12)") (class "Default")
      (node (ref "E13") (pin "12") (pinfunction "Y3_12") (pintype "output"))
    )
    (net (code "200") (name "unconnected-(E16A-Q1-Pad16)") (class "Default")
      (node (ref "E16") (pin "16") (pinfunction "Q1_16") (pintype "output"))
    )
    (net (code "201") (name "unconnected-(E16A-Q2-Pad15)") (class "Default")
      (node (ref "E16") (pin "15") (pinfunction "Q2_15") (pintype "output"))
    )
    (net (code "202") (name "unconnected-(E16A-Q4-Pad9)") (class "Default")
      (node (ref "E16") (pin "9") (pinfunction "Q4_9") (pintype "output"))
    )
    (net (code "203") (name "unconnected-(E16A-~{Q4}-Pad8)") (class "Default")
      (node (ref "E16") (pin "8") (pinfunction "~{Q4}_8") (pintype "output"))
    )
    (net (code "204") (name "unconnected-(E17A-Q-Pad15)") (class "Default")
      (node (ref "E17") (pin "15") (pinfunction "Q_15") (pintype "output"))
    )
    (net (code "205") (name "unconnected-(E17A-~{Q}-Pad14)") (class "Default")
      (node (ref "E17") (pin "14") (pinfunction "~{Q}_14") (pintype "output"))
    )
    (net (code "206") (name "unconnected-(E17B-Q-Pad11)") (class "Default")
      (node (ref "E17") (pin "11") (pinfunction "Q_11") (pintype "output"))
    )
    (net (code "207") (name "unconnected-(E19A-~{Q}-Pad6)") (class "Default")
      (node (ref "E19") (pin "6") (pinfunction "~{Q}_6") (pintype "output"))
    )
    (net (code "208") (name "unconnected-(E19B-~{Q}-Pad8)") (class "Default")
      (node (ref "E19") (pin "8") (pinfunction "~{Q}_8") (pintype "output"))
    )
    (net (code "209") (name "unconnected-(E20C-O-Pad8)") (class "Default")
      (node (ref "E20") (pin "8") (pinfunction "O_8") (pintype "output"))
    )
    (net (code "210") (name "unconnected-(E21A-~{QD}-Pad11)") (class "Default")
      (node (ref "E21") (pin "11") (pinfunction "~{QD}_11") (pintype "output"))
    )
    (net (code "211") (name "unconnected-(E22A-~{QD}-Pad11)") (class "Default")
      (node (ref "E22") (pin "11") (pinfunction "~{QD}_11") (pintype "output"))
    )
    (net (code "212") (name "unconnected-(E23A-~{QD}-Pad11)") (class "Default")
      (node (ref "E23") (pin "11") (pinfunction "~{QD}_11") (pintype "output"))
    )
    (net (code "213") (name "unconnected-(E26D-O-Pad13)") (class "Default")
      (node (ref "E26") (pin "13") (pinfunction "O_13") (pintype "output"))
    )
    (net (code "214") (name "unconnected-(E30A-~{Q}-Pad6)") (class "Default")
      (node (ref "E30") (pin "6") (pinfunction "~{Q}_6") (pintype "output"))
    )
    (net (code "215") (name "unconnected-(E30B-~{Q}-Pad8)") (class "Default")
      (node (ref "E30") (pin "8") (pinfunction "~{Q}_8") (pintype "output"))
    )
    (net (code "216") (name "unconnected-(E36D-O-Pad13)") (class "Default")
      (node (ref "E36") (pin "13") (pinfunction "O_13") (pintype "output"))
    )
    (net (code "217") (name "unconnected-(LASTDEV-Pad8)") (class "Default")
      (node (ref "LASTDEV") (pin "8") (pinfunction "8_8") (pintype "passive"))
    )
    (net (code "218") (name "unconnected-(LASTDEV-Pad9)") (class "Default")
      (node (ref "LASTDEV") (pin "9") (pinfunction "9_9") (pintype "passive"))
    )
    (net (code "219") (name "unconnected-(LASTDEV-Pad10)") (class "Default")
      (node (ref "LASTDEV") (pin "10") (pinfunction "10_10") (pintype "passive"))
    )
    (net (code "220") (name "~{ACB00}") (class "Default")
      (node (ref "D34L1") (pin "D") (pinfunction "4_D") (pintype "bidirectional"))
      (node (ref "D34L2") (pin "D") (pinfunction "4_D") (pintype "bidirectional"))
      (node (ref "IC6") (pin "3") (pinfunction "O_3") (pintype "open_collector"))
    )
    (net (code "221") (name "~{ACB01}") (class "Default")
      (node (ref "D34L1") (pin "J") (pinfunction "8_J") (pintype "bidirectional"))
      (node (ref "D34L2") (pin "J") (pinfunction "8_J") (pintype "bidirectional"))
      (node (ref "IC6") (pin "5") (pinfunction "O_5") (pintype "open_collector"))
    )
    (net (code "222") (name "~{ACB02}") (class "Default")
      (node (ref "D34L1") (pin "N") (pinfunction "12_N") (pintype "bidirectional"))
      (node (ref "D34L2") (pin "N") (pinfunction "12_N") (pintype "bidirectional"))
      (node (ref "IC1") (pin "3") (pinfunction "O_3") (pintype "open_collector"))
    )
    (net (code "223") (name "~{ACB03}") (class "Default")
      (node (ref "D34L1") (pin "T") (pinfunction "16_T") (pintype "bidirectional"))
      (node (ref "D34L2") (pin "T") (pinfunction "16_T") (pintype "bidirectional"))
      (node (ref "IC2") (pin "5") (pinfunction "O_5") (pintype "open_collector"))
    )
    (net (code "224") (name "~{ACB04}") (class "Default")
      (node (ref "D34L1") (pin "X") (pinfunction "20_X") (pintype "bidirectional"))
      (node (ref "D34L2") (pin "X") (pinfunction "20_X") (pintype "bidirectional"))
      (node (ref "IC1") (pin "5") (pinfunction "O_5") (pintype "open_collector"))
    )
    (net (code "225") (name "~{ACB05}") (class "Default")
      (node (ref "D34L1") (pin "BB") (pinfunction "24_BB") (pintype "bidirectional"))
      (node (ref "D34L2") (pin "BB") (pinfunction "24_BB") (pintype "bidirectional"))
      (node (ref "IC4") (pin "3") (pinfunction "O_3") (pintype "open_collector"))
    )
    (net (code "226") (name "~{ACB06}") (class "Default")
      (node (ref "D34L1") (pin "FF") (pinfunction "28_FF") (pintype "bidirectional"))
      (node (ref "D34L2") (pin "FF") (pinfunction "28_FF") (pintype "bidirectional"))
      (node (ref "IC3") (pin "3") (pinfunction "O_3") (pintype "open_collector"))
    )
    (net (code "227") (name "~{ACB07}") (class "Default")
      (node (ref "D34L1") (pin "LL") (pinfunction "32_LL") (pintype "bidirectional"))
      (node (ref "D34L2") (pin "LL") (pinfunction "32_LL") (pintype "bidirectional"))
      (node (ref "IC3") (pin "5") (pinfunction "O_5") (pintype "open_collector"))
    )
    (net (code "228") (name "~{ACB08}") (class "Default")
      (node (ref "D34L1") (pin "RR") (pinfunction "36_RR") (pintype "bidirectional"))
      (node (ref "D34L2") (pin "RR") (pinfunction "36_RR") (pintype "bidirectional"))
      (node (ref "IC4") (pin "5") (pinfunction "O_5") (pintype "open_collector"))
    )
    (net (code "229") (name "~{ACB09}") (class "Default")
      (node (ref "D34L1") (pin "F") (pinfunction "6_F") (pintype "bidirectional"))
      (node (ref "D34L2") (pin "F") (pinfunction "6_F") (pintype "bidirectional"))
      (node (ref "IC5") (pin "3") (pinfunction "O_3") (pintype "open_collector"))
    )
    (net (code "230") (name "~{ACB10}") (class "Default")
      (node (ref "D34L1") (pin "L") (pinfunction "10_L") (pintype "bidirectional"))
      (node (ref "D34L2") (pin "L") (pinfunction "10_L") (pintype "bidirectional"))
      (node (ref "IC5") (pin "5") (pinfunction "O_5") (pintype "open_collector"))
    )
    (net (code "231") (name "~{ACB11}") (class "Default")
      (node (ref "D34L1") (pin "R") (pinfunction "14_R") (pintype "bidirectional"))
      (node (ref "D34L2") (pin "R") (pinfunction "14_R") (pintype "bidirectional"))
      (node (ref "IC2") (pin "3") (pinfunction "O_3") (pintype "open_collector"))
    )
    (net (code "232") (name "~{ACCLEAR}") (class "Default")
      (node (ref "D34L1") (pin "DD") (pinfunction "26_DD") (pintype "bidirectional"))
      (node (ref "D34L2") (pin "DD") (pinfunction "26_DD") (pintype "bidirectional"))
      (node (ref "IC7") (pin "3") (pinfunction "O_3") (pintype "open_collector"))
    )
    (net (code "233") (name "~{BMB03}") (class "Default")
      (node (ref "D35L1") (pin "T") (pinfunction "16_T") (pintype "bidirectional"))
      (node (ref "D35L2") (pin "T") (pinfunction "16_T") (pintype "bidirectional"))
    )
    (net (code "234") (name "~{BMB04}") (class "Default")
      (node (ref "D35L1") (pin "BB") (pinfunction "24_BB") (pintype "bidirectional"))
      (node (ref "D35L2") (pin "BB") (pinfunction "24_BB") (pintype "bidirectional"))
    )
    (net (code "235") (name "~{BMB05}") (class "Default")
      (node (ref "D35L1") (pin "LL") (pinfunction "32_LL") (pintype "bidirectional"))
      (node (ref "D35L2") (pin "LL") (pinfunction "32_LL") (pintype "bidirectional"))
    )
    (net (code "236") (name "~{BMB06}") (class "Default")
      (node (ref "D35L1") (pin "F") (pinfunction "6_F") (pintype "bidirectional"))
      (node (ref "D35L2") (pin "F") (pinfunction "6_F") (pintype "bidirectional"))
    )
    (net (code "237") (name "~{BMB07}") (class "Default")
      (node (ref "D35L1") (pin "R") (pinfunction "14_R") (pintype "bidirectional"))
      (node (ref "D35L2") (pin "R") (pinfunction "14_R") (pintype "bidirectional"))
    )
    (net (code "238") (name "~{BMB08}") (class "Default")
      (node (ref "D35L1") (pin "Z") (pinfunction "22_Z") (pintype "bidirectional"))
      (node (ref "D35L2") (pin "Z") (pinfunction "22_Z") (pintype "bidirectional"))
    )
    (net (code "239") (name "~{BRUN}") (class "Default")
      (node (ref "D34L1") (pin "JJ") (pinfunction "30_JJ") (pintype "bidirectional"))
      (node (ref "D34L2") (pin "JJ") (pinfunction "30_JJ") (pintype "bidirectional"))
    )
    (net (code "240") (name "~{CLK_PARITY}") (class "Default")
      (node (ref "E17") (pin "6") (pinfunction "CLK_6") (pintype "input"))
      (node (ref "E32") (pin "6") (pinfunction "O_6") (pintype "output"))
      (node (ref "E5") (pin "4") (pinfunction "I0_4") (pintype "input"))
      (node (ref "E5") (pin "5") (pinfunction "I1_5") (pintype "input"))
    )
    (net (code "241") (name "~{DONE}") (class "Default")
      (node (ref "E10") (pin "4") (pinfunction "I1_4") (pintype "input"))
      (node (ref "E25") (pin "4") (pinfunction "O_4") (pintype "output"))
      (node (ref "E31") (pin "12") (pinfunction "I2_12") (pintype "input"))
    )
    (net (code "242") (name "~{ENB_BUF_LD}") (class "Default")
      (node (ref "E21") (pin "9") (pinfunction "S/~{L}_9") (pintype "input"))
      (node (ref "E22") (pin "9") (pinfunction "S/~{L}_9") (pintype "input"))
      (node (ref "E23") (pin "9") (pinfunction "S/~{L}_9") (pintype "input"))
      (node (ref "E24") (pin "11") (pinfunction "O_11") (pintype "output"))
      (node (ref "E32") (pin "13") (pinfunction "I2_13") (pintype "input"))
      (node (ref "E32") (pin "2") (pinfunction "I1_2") (pintype "input"))
      (node (ref "E4") (pin "9") (pinfunction "LD_9") (pintype "input"))
    )
    (net (code "243") (name "~{INIT1}") (class "Default")
      (node (ref "E11") (pin "7") (pinfunction "Y7_7") (pintype "output"))
      (node (ref "E2") (pin "4") (pinfunction "PRE_4") (pintype "input"))
    )
    (net (code "244") (name "~{INIT4}") (class "Default")
      (node (ref "E13") (pin "7") (pinfunction "Y7_7") (pintype "output"))
      (node (ref "E2") (pin "3") (pinfunction "CLK_3") (pintype "input"))
    )
    (net (code "245") (name "~{INIT}") (class "Default")
      (node (ref "E15") (pin "6") (pinfunction "O_6") (pintype "output"))
      (node (ref "E2") (pin "13") (pinfunction "CLR_13") (pintype "input"))
      (node (ref "E21") (pin "1") (pinfunction "CLR_1") (pintype "input"))
      (node (ref "E22") (pin "1") (pinfunction "CLR_1") (pintype "input"))
      (node (ref "E23") (pin "1") (pinfunction "CLR_1") (pintype "input"))
      (node (ref "E24") (pin "9") (pinfunction "I0_9") (pintype "input"))
      (node (ref "E30") (pin "1") (pinfunction "CLR_1") (pintype "input"))
      (node (ref "E4") (pin "1") (pinfunction "CLR_1") (pintype "input"))
      (node (ref "E6") (pin "1") (pinfunction "CLR_1") (pintype "input"))
    )
    (net (code "246") (name "~{INTR4}") (class "Default")
      (node (ref "E13") (pin "9") (pinfunction "Y6_9") (pintype "output"))
      (node (ref "E30") (pin "3") (pinfunction "CLK_3") (pintype "input"))
    )
    (net (code "247") (name "~{INT_RQ}") (class "Default")
      (node (ref "D34L1") (pin "Z") (pinfunction "22_Z") (pintype "bidirectional"))
      (node (ref "D34L2") (pin "Z") (pinfunction "22_Z") (pintype "bidirectional"))
      (node (ref "IC10") (pin "5") (pinfunction "O_5") (pintype "open_collector"))
    )
    (net (code "248") (name "~{IOS}") (class "Default")
      (node (ref "D34L1") (pin "V") (pinfunction "18_V") (pintype "bidirectional"))
      (node (ref "D34L2") (pin "V") (pinfunction "18_V") (pintype "bidirectional"))
      (node (ref "IC10") (pin "3") (pinfunction "O_3") (pintype "open_collector"))
    )
    (net (code "249") (name "~{LCD1}") (class "Default")
      (node (ref "E10") (pin "9") (pinfunction "I0_9") (pintype "input"))
      (node (ref "E11") (pin "14") (pinfunction "Y1_14") (pintype "output"))
      (node (ref "E2") (pin "11") (pinfunction "CLK_11") (pintype "input"))
      (node (ref "E24") (pin "5") (pinfunction "I1_5") (pintype "input"))
      (node (ref "E25") (pin "5") (pinfunction "I_5") (pintype "input"))
      (node (ref "E6") (pin "3") (pinfunction "CLK_3") (pintype "input"))
    )
    (net (code "250") (name "~{MAINT}") (class "Default")
      (node (ref "E10") (pin "3") (pinfunction "I0_3") (pintype "input"))
      (node (ref "E19") (pin "10") (pinfunction "PRE_10") (pintype "input"))
      (node (ref "E19") (pin "4") (pinfunction "PRE_4") (pintype "input"))
      (node (ref "E24") (pin "13") (pinfunction "I1_13") (pintype "input"))
      (node (ref "E31") (pin "10") (pinfunction "I1_10") (pintype "input"))
      (node (ref "E31") (pin "5") (pinfunction "I3_5") (pintype "input"))
      (node (ref "E31") (pin "9") (pinfunction "I0_9") (pintype "input"))
      (node (ref "E6") (pin "10") (pinfunction "PRE_10") (pintype "input"))
      (node (ref "E6") (pin "6") (pinfunction "~{Q}_6") (pintype "output"))
    )
    (net (code "251") (name "~{MYDEV}") (class "Default")
      (node (ref "E11") (pin "4") (pinfunction "G2A_4") (pintype "input"))
      (node (ref "E12") (pin "4") (pinfunction "G2A_4") (pintype "input"))
      (node (ref "E13") (pin "4") (pinfunction "G2A_4") (pintype "input"))
      (node (ref "IOT") (pin "1") (pinfunction "P_1") (pintype "passive"))
    )
    (net (code "252") (name "~{PARITY}") (class "Default")
      (node (ref "E15") (pin "12") (pinfunction "I0_12") (pintype "input"))
      (node (ref "E17") (pin "10") (pinfunction "~{Q}_10") (pintype "output"))
    )
    (net (code "253") (name "~{RX_12_BIT}") (class "Default")
      (node (ref "DRIVE") (pin "FF") (pinfunction "28_FF") (pintype "bidirectional"))
      (node (ref "IC8") (pin "3") (pinfunction "O_3") (pintype "open_collector"))
      (node (ref "R16") (pin "2") (pinfunction "2_2") (pintype "passive"))
      (node (ref "R7") (pin "1") (pinfunction "1_1") (pintype "passive"))
    )
    (net (code "254") (name "~{RX_DATA}") (class "Default")
      (node (ref "DRIVE") (pin "BB") (pinfunction "24_BB") (pintype "bidirectional"))
      (node (ref "E35") (pin "2") (pinfunction "I0_2") (pintype "input"))
      (node (ref "IC7") (pin "5") (pinfunction "O_5") (pintype "open_collector"))
      (node (ref "R17") (pin "2") (pinfunction "2_2") (pintype "passive"))
      (node (ref "R8") (pin "1") (pinfunction "1_1") (pintype "passive"))
    )
    (net (code "255") (name "~{RX_DONE}") (class "Default")
      (node (ref "DRIVE") (pin "X") (pinfunction "20_X") (pintype "bidirectional"))
      (node (ref "E36") (pin "8") (pinfunction "I0_8") (pintype "input"))
      (node (ref "R13") (pin "2") (pinfunction "2_2") (pintype "passive"))
      (node (ref "R4") (pin "1") (pinfunction "1_1") (pintype "passive"))
    )
    (net (code "256") (name "~{RX_ERROR}") (class "Default")
      (node (ref "DRIVE") (pin "J") (pinfunction "8_J") (pintype "bidirectional"))
      (node (ref "E36") (pin "3") (pinfunction "I1_3") (pintype "input"))
      (node (ref "R14") (pin "2") (pinfunction "2_2") (pintype "passive"))
      (node (ref "R5") (pin "1") (pinfunction "1_1") (pintype "passive"))
    )
    (net (code "257") (name "~{RX_INIT}") (class "Default")
      (node (ref "DRIVE") (pin "N") (pinfunction "12_N") (pintype "bidirectional"))
      (node (ref "IC8") (pin "5") (pinfunction "O_5") (pintype "open_collector"))
      (node (ref "R20") (pin "1") (pinfunction "1_1") (pintype "passive"))
      (node (ref "R9") (pin "1") (pinfunction "1_1") (pintype "passive"))
    )
    (net (code "258") (name "~{RX_OUT}") (class "Default")
      (node (ref "DRIVE") (pin "RR") (pinfunction "36_RR") (pintype "bidirectional"))
      (node (ref "E35") (pin "8") (pinfunction "I0_8") (pintype "input"))
      (node (ref "R12") (pin "2") (pinfunction "2_2") (pintype "passive"))
      (node (ref "R3") (pin "1") (pinfunction "1_1") (pintype "passive"))
    )
    (net (code "259") (name "~{RX_RUN}") (class "Default")
      (node (ref "DRIVE") (pin "D") (pinfunction "4_D") (pintype "bidirectional"))
      (node (ref "IC9") (pin "5") (pinfunction "O_5") (pintype "open_collector"))
      (node (ref "R15") (pin "2") (pinfunction "2_2") (pintype "passive"))
      (node (ref "R6") (pin "1") (pinfunction "1_1") (pintype "passive"))
    )
    (net (code "260") (name "~{RX_SHIFT}") (class "Default")
      (node (ref "DRIVE") (pin "LL") (pinfunction "32_LL") (pintype "bidirectional"))
      (node (ref "E35") (pin "5") (pinfunction "I0_5") (pintype "input"))
      (node (ref "R10") (pin "2") (pinfunction "2_2") (pintype "passive"))
      (node (ref "R2") (pin "1") (pinfunction "1_1") (pintype "passive"))
    )
    (net (code "261") (name "~{RX_TR_REQ}") (class "Default")
      (node (ref "DRIVE") (pin "T") (pinfunction "16_T") (pintype "bidirectional"))
      (node (ref "E36") (pin "5") (pinfunction "I0_5") (pintype "input"))
      (node (ref "R1") (pin "1") (pinfunction "1_1") (pintype "passive"))
      (node (ref "R11") (pin "2") (pinfunction "2_2") (pintype "passive"))
    )
    (net (code "262") (name "~{SDN4}") (class "Default")
      (node (ref "E13") (pin "10") (pinfunction "Y5_10") (pintype "output"))
      (node (ref "E18") (pin "8") (pinfunction "I0_8") (pintype "input"))
    )
    (net (code "263") (name "~{SER4}") (class "Default")
      (node (ref "E13") (pin "11") (pinfunction "Y4_11") (pintype "output"))
      (node (ref "E18") (pin "5") (pinfunction "I0_5") (pintype "input"))
    )
    (net (code "264") (name "~{STR2}") (class "Default")
      (node (ref "E12") (pin "12") (pinfunction "Y3_12") (pintype "output"))
      (node (ref "E18") (pin "2") (pinfunction "I0_2") (pintype "input"))
    )
    (net (code "265") (name "~{XDR2}") (class "Default")
      (node (ref "E12") (pin "13") (pinfunction "Y2_13") (pintype "output"))
      (node (ref "E24") (pin "4") (pinfunction "I0_4") (pintype "input"))
      (node (ref "E25") (pin "9") (pinfunction "I_9") (pintype "input"))
      (node (ref "E35") (pin "12") (pinfunction "I1_12") (pintype "input"))
      (node (ref "E5") (pin "10") (pinfunction "I1_10") (pintype "input"))
      (node (ref "E5") (pin "9") (pinfunction "I0_9") (pintype "input"))
    )
  )
)
